# microzed_breakout_v0_7_b6e30659.net
KiCad netlist of a schematic drawn in EAGLE
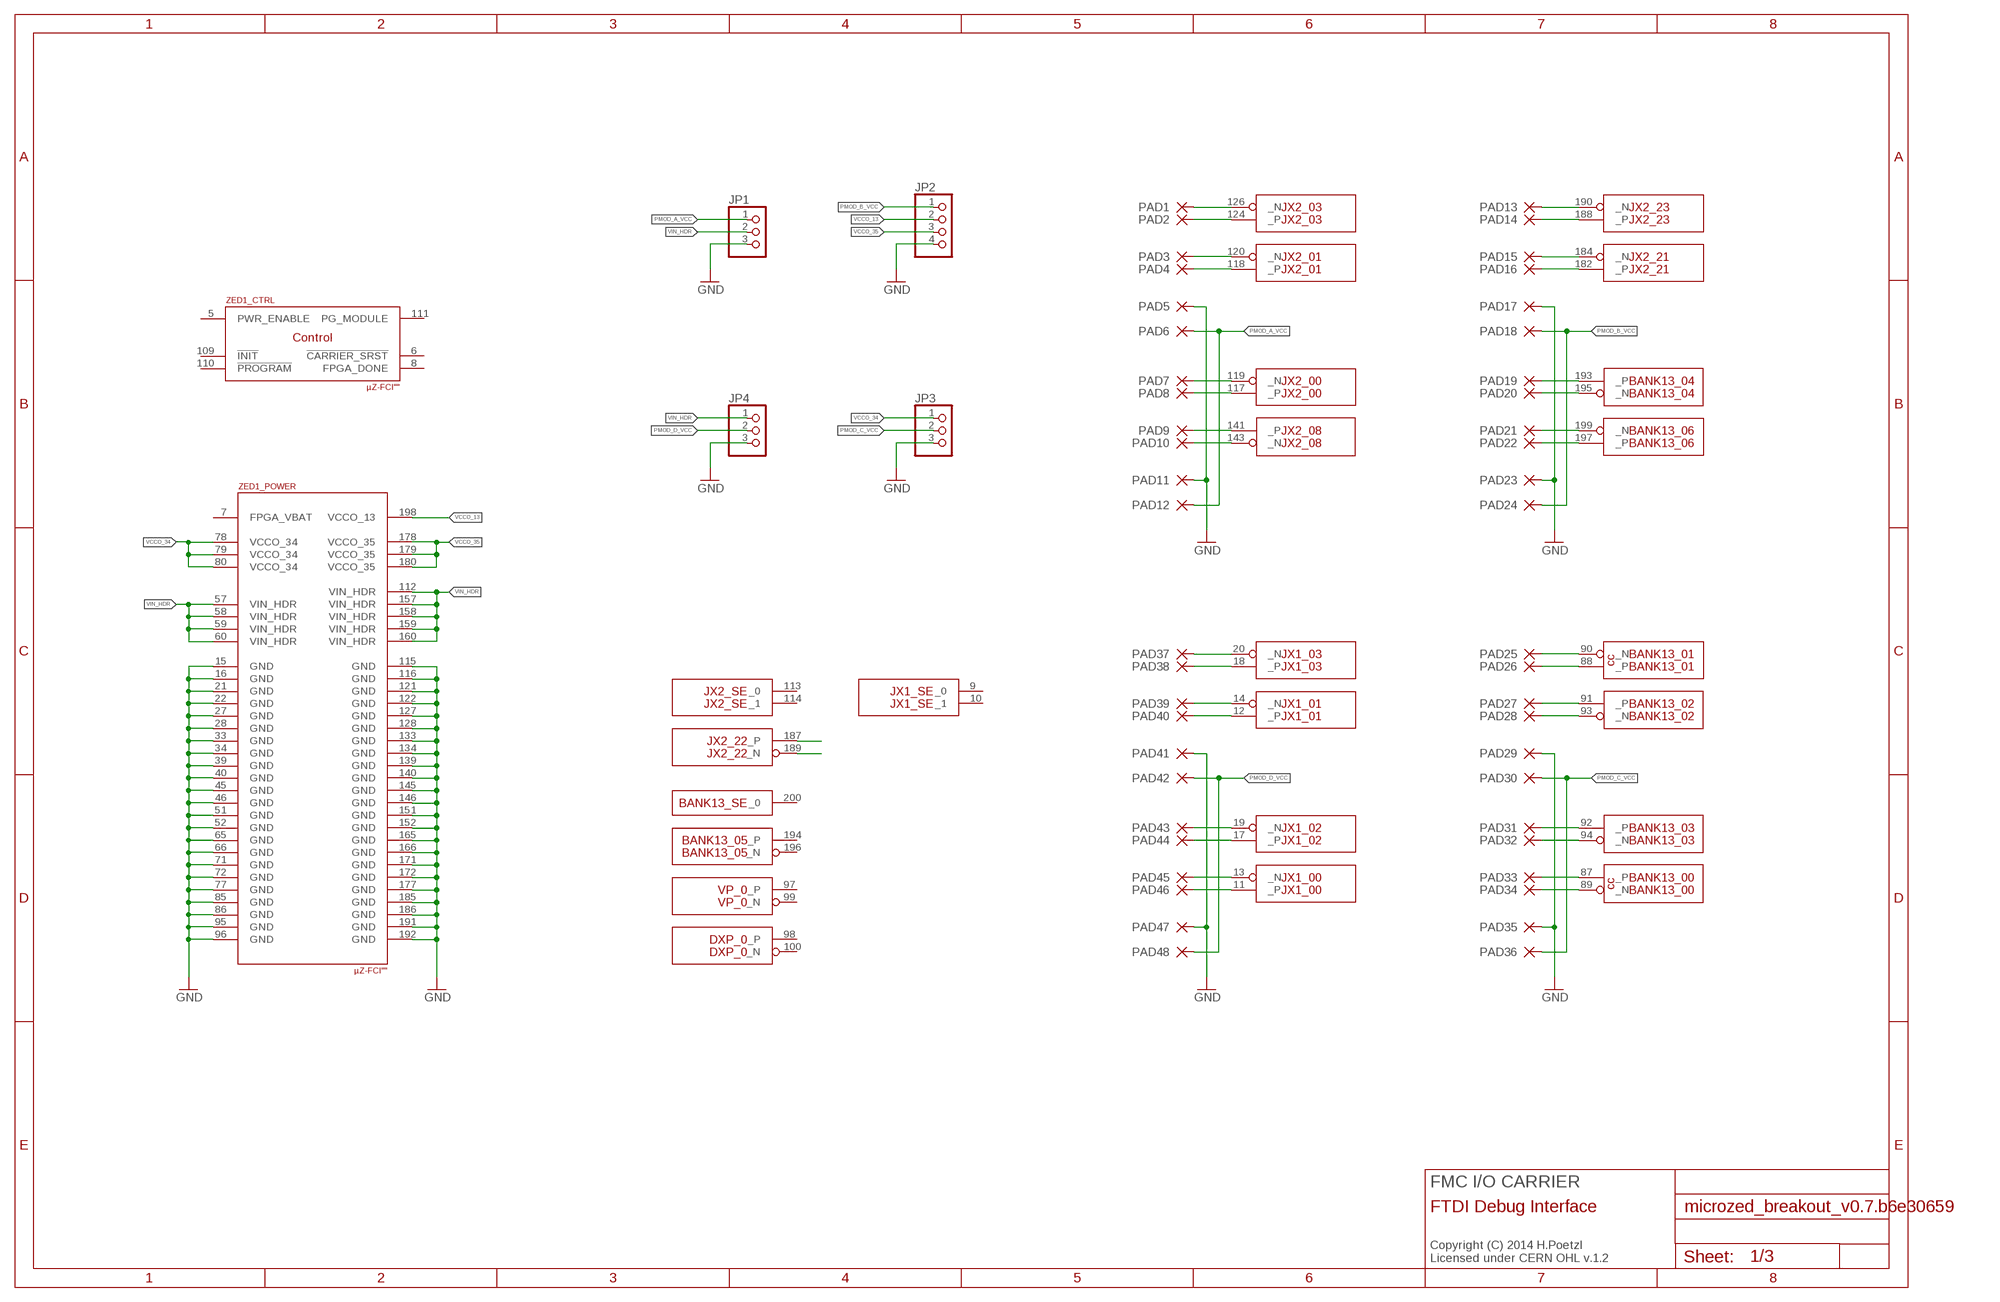
[diagram p0: schematic, sheet 1]
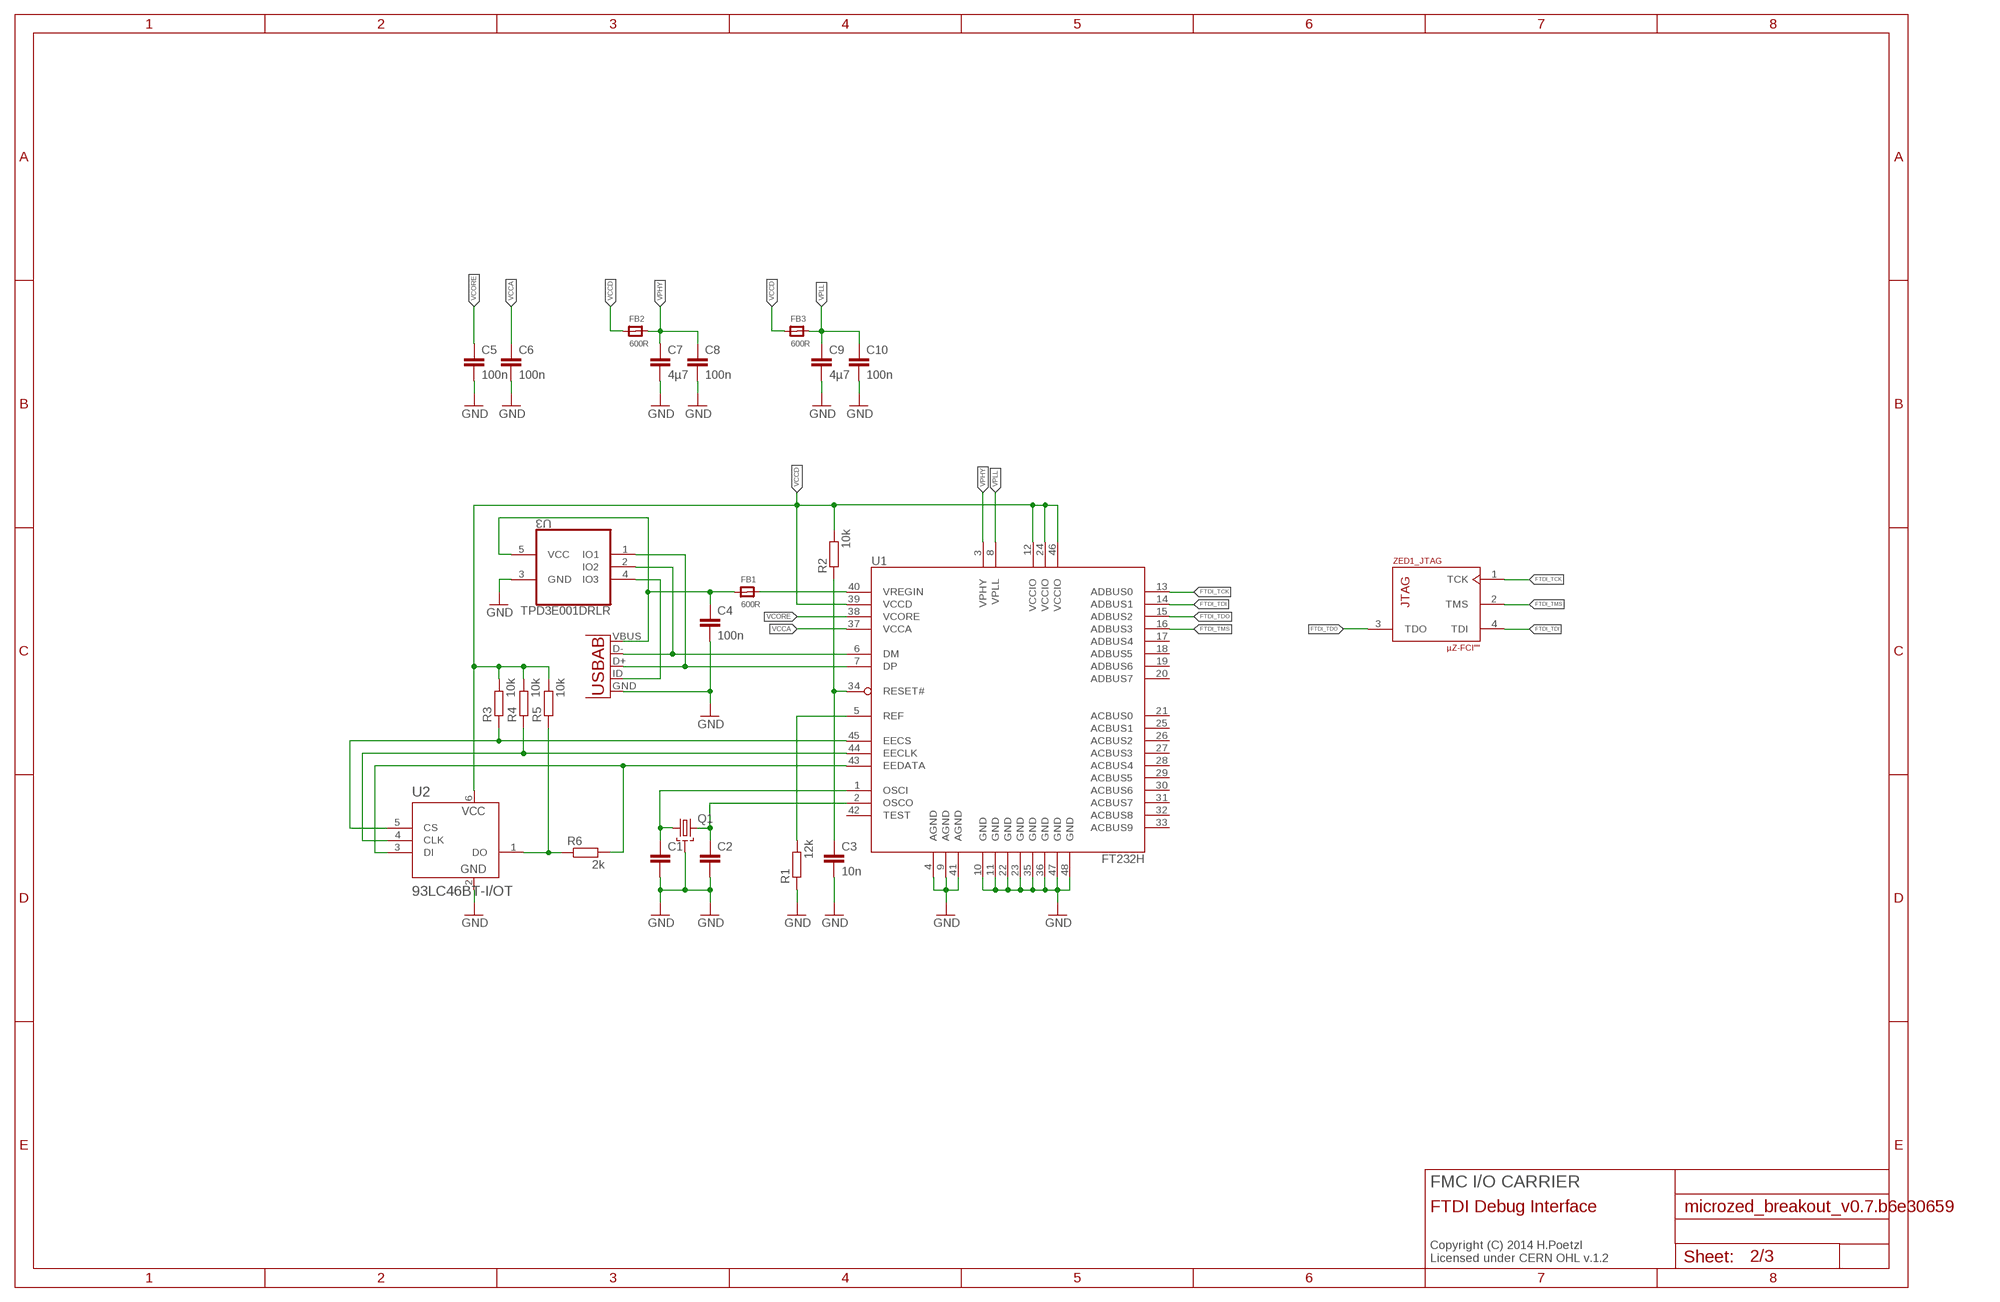
[diagram p1: schematic, sheet 2]
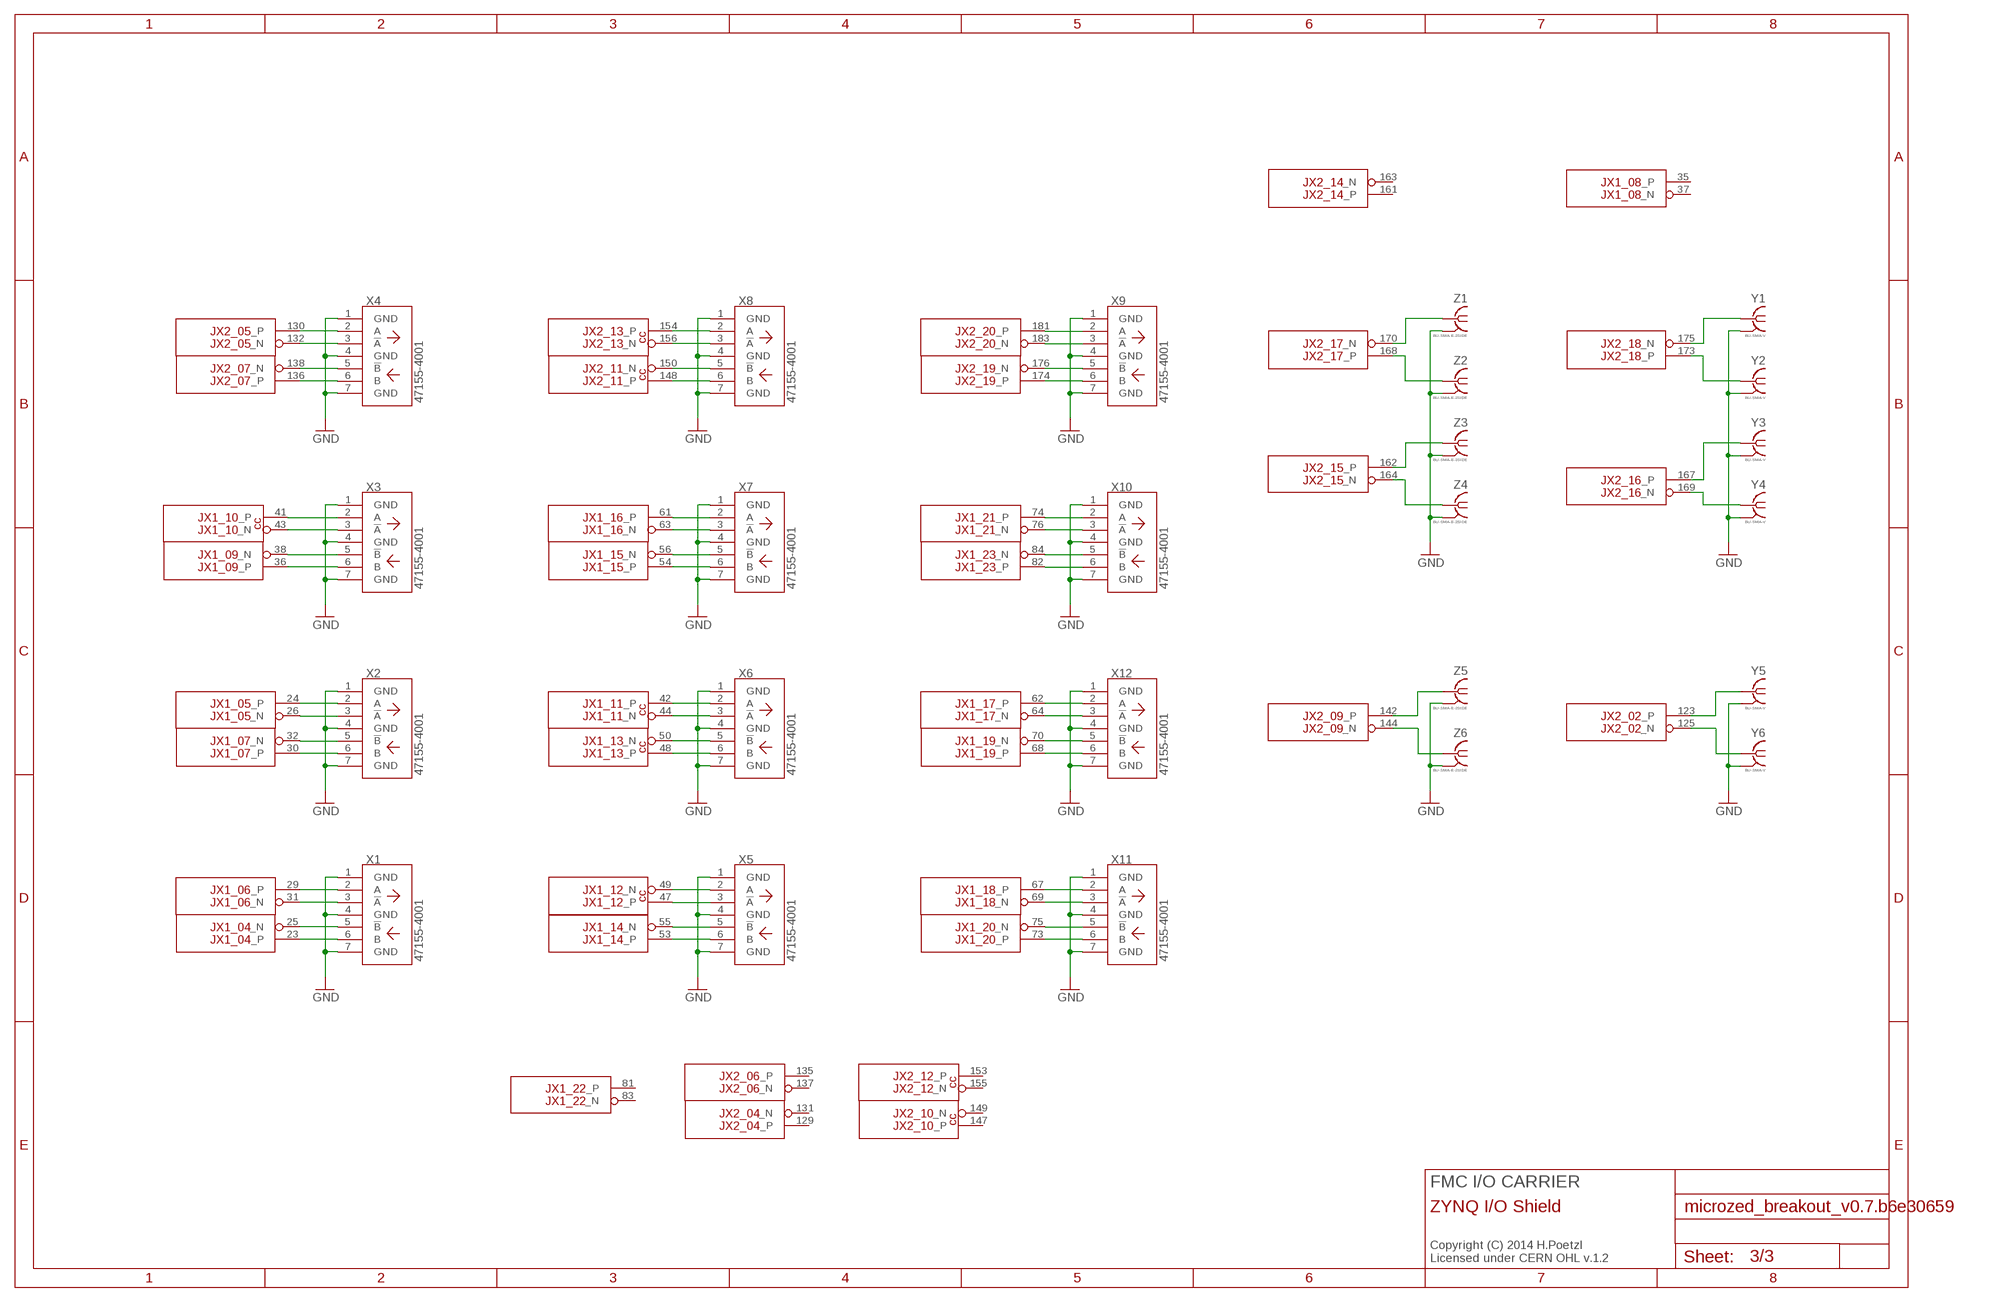
[diagram p2: schematic, sheet 3]

(export (version "E")
  (design (tool "Eeschema 10.0.6"))
  (components
    (comp (ref "C1")
      (value "C-EUC0402K")
      (footprint "eagle-import:C0402K")
      (libsource (lib "eagle-import") (part "C-EUC0402K"))
    )
    (comp (ref "C2")
      (value "C-EUC0402K")
      (footprint "eagle-import:C0402K")
      (libsource (lib "eagle-import") (part "C-EUC0402K"))
    )
    (comp (ref "C3")
      (value "10n")
      (footprint "eagle-import:C0402K")
      (libsource (lib "eagle-import") (part "C-EUC0402K"))
    )
    (comp (ref "C4")
      (value "100n")
      (footprint "eagle-import:C0402K")
      (libsource (lib "eagle-import") (part "C-EUC0402K"))
    )
    (comp (ref "C5")
      (value "100n")
      (footprint "eagle-import:C0402K")
      (libsource (lib "eagle-import") (part "C-EUC0402K"))
    )
    (comp (ref "C6")
      (value "100n")
      (footprint "eagle-import:C0402K")
      (libsource (lib "eagle-import") (part "C-EUC0402K"))
    )
    (comp (ref "C7")
      (value "4µ7")
      (footprint "eagle-import:C0402K")
      (libsource (lib "eagle-import") (part "C-EUC0402K"))
    )
    (comp (ref "C8")
      (value "100n")
      (footprint "eagle-import:C0402K")
      (libsource (lib "eagle-import") (part "C-EUC0402K"))
    )
    (comp (ref "C9")
      (value "4µ7")
      (footprint "eagle-import:C0402K")
      (libsource (lib "eagle-import") (part "C-EUC0402K"))
    )
    (comp (ref "C10")
      (value "100n")
      (footprint "eagle-import:C0402K")
      (libsource (lib "eagle-import") (part "C-EUC0402K"))
    )
    (comp (ref "FB1")
      (value "600R")
      (footprint "eagle-import:_0603MP")
      (libsource (lib "eagle-import") (part "FERRITE_0603MP"))
    )
    (comp (ref "FB2")
      (value "600R")
      (footprint "eagle-import:_0603MP")
      (libsource (lib "eagle-import") (part "FERRITE_0603MP"))
    )
    (comp (ref "FB3")
      (value "600R")
      (footprint "eagle-import:_0603MP")
      (libsource (lib "eagle-import") (part "FERRITE_0603MP"))
    )
    (comp (ref "Q1")
      (value "SMD-4P-2G-3.2X2.5")
      (footprint "eagle-import:ABM8G")
      (libsource (lib "eagle-import") (part "SMD-4P-2G-3.2X2.5"))
    )
    (comp (ref "R1")
      (value "12k")
      (footprint "eagle-import:R0402")
      (libsource (lib "eagle-import") (part "R-EU_R0402"))
    )
    (comp (ref "R2")
      (value "10k")
      (footprint "eagle-import:R0402")
      (libsource (lib "eagle-import") (part "R-EU_R0402"))
    )
    (comp (ref "R3")
      (value "10k")
      (footprint "eagle-import:R0402")
      (libsource (lib "eagle-import") (part "R-EU_R0402"))
    )
    (comp (ref "R4")
      (value "10k")
      (footprint "eagle-import:R0402")
      (libsource (lib "eagle-import") (part "R-EU_R0402"))
    )
    (comp (ref "R5")
      (value "10k")
      (footprint "eagle-import:R0402")
      (libsource (lib "eagle-import") (part "R-EU_R0402"))
    )
    (comp (ref "R6")
      (value "2k")
      (footprint "eagle-import:R0402")
      (libsource (lib "eagle-import") (part "R-EU_R0402"))
    )
    (comp (ref "U1")
      (value "FT232H")
      (footprint "eagle-import:LQFP48")
      (libsource (lib "eagle-import") (part "FT232H"))
    )
    (comp (ref "U2")
      (value "93LC46BT-I/OT")
      (footprint "eagle-import:SOT95P280X145-6N")
      (libsource (lib "eagle-import") (part "93LC46BT-I/OT"))
    )
    (comp (ref "U3")
      (value "TPD3E001DRLR")
      (footprint "eagle-import:SOT50P160X60-5N")
      (libsource (lib "eagle-import") (part "TPD3E001DRLR"))
    )
    (comp (ref "USB")
      (value "USB-AB")
      (footprint "eagle-import:USB-AB-MICRO-SMD")
      (libsource (lib "eagle-import") (part "USB-AB"))
    )
    (comp (ref "ZED1")
      (value "µZ-FCI\"\"")
      (footprint "eagle-import:µZ")
      (libsource (lib "eagle-import") (part "µZ-FCI{dblquote}{dblquote}"))
    )
    (comp (ref "X1")
      (value "47155-4001")
      (footprint "eagle-import:SATA7-VERT")
      (libsource (lib "eagle-import") (part "SATA7-VERT"))
    )
    (comp (ref "X2")
      (value "47155-4001")
      (footprint "eagle-import:SATA7-VERT")
      (libsource (lib "eagle-import") (part "SATA7-VERT"))
    )
    (comp (ref "X3")
      (value "47155-4001")
      (footprint "eagle-import:SATA7-VERT")
      (libsource (lib "eagle-import") (part "SATA7-VERT"))
    )
    (comp (ref "X4")
      (value "47155-4001")
      (footprint "eagle-import:SATA7-VERT")
      (libsource (lib "eagle-import") (part "SATA7-VERT"))
    )
    (comp (ref "X5")
      (value "47155-4001")
      (footprint "eagle-import:SATA7-VERT")
      (libsource (lib "eagle-import") (part "SATA7-VERT"))
    )
    (comp (ref "X6")
      (value "47155-4001")
      (footprint "eagle-import:SATA7-VERT")
      (libsource (lib "eagle-import") (part "SATA7-VERT"))
    )
    (comp (ref "X7")
      (value "47155-4001")
      (footprint "eagle-import:SATA7-VERT")
      (libsource (lib "eagle-import") (part "SATA7-VERT"))
    )
    (comp (ref "X8")
      (value "47155-4001")
      (footprint "eagle-import:SATA7-VERT")
      (libsource (lib "eagle-import") (part "SATA7-VERT"))
    )
    (comp (ref "X9")
      (value "47155-4001")
      (footprint "eagle-import:SATA7-VERT")
      (libsource (lib "eagle-import") (part "SATA7-VERT"))
    )
    (comp (ref "X10")
      (value "47155-4001")
      (footprint "eagle-import:SATA7-VERT")
      (libsource (lib "eagle-import") (part "SATA7-VERT"))
    )
    (comp (ref "X11")
      (value "47155-4001")
      (footprint "eagle-import:SATA7-VERT")
      (libsource (lib "eagle-import") (part "SATA7-VERT"))
    )
    (comp (ref "X12")
      (value "47155-4001")
      (footprint "eagle-import:SATA7-VERT")
      (libsource (lib "eagle-import") (part "SATA7-VERT"))
    )
    (comp (ref "Y1")
      (value "BU-SMA-V")
      (footprint "eagle-import:BU-SMA-V")
      (libsource (lib "eagle-import") (part "BU-SMA-V"))
    )
    (comp (ref "Y2")
      (value "BU-SMA-V")
      (footprint "eagle-import:BU-SMA-V")
      (libsource (lib "eagle-import") (part "BU-SMA-V"))
    )
    (comp (ref "Y3")
      (value "BU-SMA-V")
      (footprint "eagle-import:BU-SMA-V")
      (libsource (lib "eagle-import") (part "BU-SMA-V"))
    )
    (comp (ref "Y4")
      (value "BU-SMA-V")
      (footprint "eagle-import:BU-SMA-V")
      (libsource (lib "eagle-import") (part "BU-SMA-V"))
    )
    (comp (ref "Y5")
      (value "BU-SMA-V")
      (footprint "eagle-import:BU-SMA-V")
      (libsource (lib "eagle-import") (part "BU-SMA-V"))
    )
    (comp (ref "Y6")
      (value "BU-SMA-V")
      (footprint "eagle-import:BU-SMA-V")
      (libsource (lib "eagle-import") (part "BU-SMA-V"))
    )
    (comp (ref "Z1")
      (value "BU-SMA-E-2SIDE")
      (footprint "eagle-import:SMA_EDGE_2SIDE")
      (libsource (lib "eagle-import") (part "BU-SMA-E-2SIDE"))
    )
    (comp (ref "Z2")
      (value "BU-SMA-E-2SIDE")
      (footprint "eagle-import:SMA_EDGE_2SIDE")
      (libsource (lib "eagle-import") (part "BU-SMA-E-2SIDE"))
    )
    (comp (ref "Z3")
      (value "BU-SMA-E-2SIDE")
      (footprint "eagle-import:SMA_EDGE_2SIDE")
      (libsource (lib "eagle-import") (part "BU-SMA-E-2SIDE"))
    )
    (comp (ref "Z4")
      (value "BU-SMA-E-2SIDE")
      (footprint "eagle-import:SMA_EDGE_2SIDE")
      (libsource (lib "eagle-import") (part "BU-SMA-E-2SIDE"))
    )
    (comp (ref "Z5")
      (value "BU-SMA-E-2SIDE")
      (footprint "eagle-import:SMA_EDGE_2SIDE")
      (libsource (lib "eagle-import") (part "BU-SMA-E-2SIDE"))
    )
    (comp (ref "Z6")
      (value "BU-SMA-E-2SIDE")
      (footprint "eagle-import:SMA_EDGE_2SIDE")
      (libsource (lib "eagle-import") (part "BU-SMA-E-2SIDE"))
    )
    (comp (ref "JP1")
      (value "PINHD-1X03_2.54")
      (footprint "eagle-import:1X03")
      (libsource (lib "eagle-import") (part "PINHD-1X03_2.54"))
    )
    (comp (ref "JP2")
      (value "PINHD-1X04_2.54")
      (footprint "eagle-import:1X04")
      (libsource (lib "eagle-import") (part "PINHD-1X04_2.54"))
    )
    (comp (ref "JP3")
      (value "PINHD-1X03_2.54")
      (footprint "eagle-import:1X03")
      (libsource (lib "eagle-import") (part "PINHD-1X03_2.54"))
    )
    (comp (ref "JP4")
      (value "PINHD-1X03_2.54")
      (footprint "eagle-import:1X03")
      (libsource (lib "eagle-import") (part "PINHD-1X03_2.54"))
    )
    (comp (ref "PAD1")
      (value "SMD-PAD1.6X3.8MM-U")
      (footprint "eagle-import:1.6X3.8U-MM")
      (libsource (lib "eagle-import") (part "SMD-PAD1.6X3.8MM-U"))
    )
    (comp (ref "PAD2")
      (value "SMD-PAD1.6X3.8MM-U")
      (footprint "eagle-import:1.6X3.8U-MM")
      (libsource (lib "eagle-import") (part "SMD-PAD1.6X3.8MM-U"))
    )
    (comp (ref "PAD3")
      (value "SMD-PAD1.6X3.8MM-U")
      (footprint "eagle-import:1.6X3.8U-MM")
      (libsource (lib "eagle-import") (part "SMD-PAD1.6X3.8MM-U"))
    )
    (comp (ref "PAD4")
      (value "SMD-PAD1.6X3.8MM-U")
      (footprint "eagle-import:1.6X3.8U-MM")
      (libsource (lib "eagle-import") (part "SMD-PAD1.6X3.8MM-U"))
    )
    (comp (ref "PAD5")
      (value "SMD-PAD1.6X3.8MM-U")
      (footprint "eagle-import:1.6X3.8U-MM")
      (libsource (lib "eagle-import") (part "SMD-PAD1.6X3.8MM-U"))
    )
    (comp (ref "PAD6")
      (value "SMD-PAD1.6X3.8MM-U")
      (footprint "eagle-import:1.6X3.8U-MM")
      (libsource (lib "eagle-import") (part "SMD-PAD1.6X3.8MM-U"))
    )
    (comp (ref "PAD7")
      (value "SMD-PAD1.6X3.8MM-U")
      (footprint "eagle-import:1.6X3.8U-MM")
      (libsource (lib "eagle-import") (part "SMD-PAD1.6X3.8MM-U"))
    )
    (comp (ref "PAD8")
      (value "SMD-PAD1.6X3.8MM-U")
      (footprint "eagle-import:1.6X3.8U-MM")
      (libsource (lib "eagle-import") (part "SMD-PAD1.6X3.8MM-U"))
    )
    (comp (ref "PAD9")
      (value "SMD-PAD1.6X3.8MM-U")
      (footprint "eagle-import:1.6X3.8U-MM")
      (libsource (lib "eagle-import") (part "SMD-PAD1.6X3.8MM-U"))
    )
    (comp (ref "PAD10")
      (value "SMD-PAD1.6X3.8MM-U")
      (footprint "eagle-import:1.6X3.8U-MM")
      (libsource (lib "eagle-import") (part "SMD-PAD1.6X3.8MM-U"))
    )
    (comp (ref "PAD11")
      (value "SMD-PAD1.6X3.8MM-U")
      (footprint "eagle-import:1.6X3.8U-MM")
      (libsource (lib "eagle-import") (part "SMD-PAD1.6X3.8MM-U"))
    )
    (comp (ref "PAD12")
      (value "SMD-PAD1.6X3.8MM-U")
      (footprint "eagle-import:1.6X3.8U-MM")
      (libsource (lib "eagle-import") (part "SMD-PAD1.6X3.8MM-U"))
    )
    (comp (ref "PAD13")
      (value "SMD-PAD1.6X3.8MM-U")
      (footprint "eagle-import:1.6X3.8U-MM")
      (libsource (lib "eagle-import") (part "SMD-PAD1.6X3.8MM-U"))
    )
    (comp (ref "PAD14")
      (value "SMD-PAD1.6X3.8MM-U")
      (footprint "eagle-import:1.6X3.8U-MM")
      (libsource (lib "eagle-import") (part "SMD-PAD1.6X3.8MM-U"))
    )
    (comp (ref "PAD15")
      (value "SMD-PAD1.6X3.8MM-U")
      (footprint "eagle-import:1.6X3.8U-MM")
      (libsource (lib "eagle-import") (part "SMD-PAD1.6X3.8MM-U"))
    )
    (comp (ref "PAD16")
      (value "SMD-PAD1.6X3.8MM-U")
      (footprint "eagle-import:1.6X3.8U-MM")
      (libsource (lib "eagle-import") (part "SMD-PAD1.6X3.8MM-U"))
    )
    (comp (ref "PAD17")
      (value "SMD-PAD1.6X3.8MM-U")
      (footprint "eagle-import:1.6X3.8U-MM")
      (libsource (lib "eagle-import") (part "SMD-PAD1.6X3.8MM-U"))
    )
    (comp (ref "PAD18")
      (value "SMD-PAD1.6X3.8MM-U")
      (footprint "eagle-import:1.6X3.8U-MM")
      (libsource (lib "eagle-import") (part "SMD-PAD1.6X3.8MM-U"))
    )
    (comp (ref "PAD19")
      (value "SMD-PAD1.6X3.8MM-U")
      (footprint "eagle-import:1.6X3.8U-MM")
      (libsource (lib "eagle-import") (part "SMD-PAD1.6X3.8MM-U"))
    )
    (comp (ref "PAD20")
      (value "SMD-PAD1.6X3.8MM-U")
      (footprint "eagle-import:1.6X3.8U-MM")
      (libsource (lib "eagle-import") (part "SMD-PAD1.6X3.8MM-U"))
    )
    (comp (ref "PAD21")
      (value "SMD-PAD1.6X3.8MM-U")
      (footprint "eagle-import:1.6X3.8U-MM")
      (libsource (lib "eagle-import") (part "SMD-PAD1.6X3.8MM-U"))
    )
    (comp (ref "PAD22")
      (value "SMD-PAD1.6X3.8MM-U")
      (footprint "eagle-import:1.6X3.8U-MM")
      (libsource (lib "eagle-import") (part "SMD-PAD1.6X3.8MM-U"))
    )
    (comp (ref "PAD23")
      (value "SMD-PAD1.6X3.8MM-U")
      (footprint "eagle-import:1.6X3.8U-MM")
      (libsource (lib "eagle-import") (part "SMD-PAD1.6X3.8MM-U"))
    )
    (comp (ref "PAD24")
      (value "SMD-PAD1.6X3.8MM-U")
      (footprint "eagle-import:1.6X3.8U-MM")
      (libsource (lib "eagle-import") (part "SMD-PAD1.6X3.8MM-U"))
    )
    (comp (ref "PAD25")
      (value "SMD-PAD1.6X3.8MM-U")
      (footprint "eagle-import:1.6X3.8U-MM")
      (libsource (lib "eagle-import") (part "SMD-PAD1.6X3.8MM-U"))
    )
    (comp (ref "PAD26")
      (value "SMD-PAD1.6X3.8MM-U")
      (footprint "eagle-import:1.6X3.8U-MM")
      (libsource (lib "eagle-import") (part "SMD-PAD1.6X3.8MM-U"))
    )
    (comp (ref "PAD27")
      (value "SMD-PAD1.6X3.8MM-U")
      (footprint "eagle-import:1.6X3.8U-MM")
      (libsource (lib "eagle-import") (part "SMD-PAD1.6X3.8MM-U"))
    )
    (comp (ref "PAD28")
      (value "SMD-PAD1.6X3.8MM-U")
      (footprint "eagle-import:1.6X3.8U-MM")
      (libsource (lib "eagle-import") (part "SMD-PAD1.6X3.8MM-U"))
    )
    (comp (ref "PAD29")
      (value "SMD-PAD1.6X3.8MM-U")
      (footprint "eagle-import:1.6X3.8U-MM")
      (libsource (lib "eagle-import") (part "SMD-PAD1.6X3.8MM-U"))
    )
    (comp (ref "PAD30")
      (value "SMD-PAD1.6X3.8MM-U")
      (footprint "eagle-import:1.6X3.8U-MM")
      (libsource (lib "eagle-import") (part "SMD-PAD1.6X3.8MM-U"))
    )
    (comp (ref "PAD31")
      (value "SMD-PAD1.6X3.8MM-U")
      (footprint "eagle-import:1.6X3.8U-MM")
      (libsource (lib "eagle-import") (part "SMD-PAD1.6X3.8MM-U"))
    )
    (comp (ref "PAD32")
      (value "SMD-PAD1.6X3.8MM-U")
      (footprint "eagle-import:1.6X3.8U-MM")
      (libsource (lib "eagle-import") (part "SMD-PAD1.6X3.8MM-U"))
    )
    (comp (ref "PAD33")
      (value "SMD-PAD1.6X3.8MM-U")
      (footprint "eagle-import:1.6X3.8U-MM")
      (libsource (lib "eagle-import") (part "SMD-PAD1.6X3.8MM-U"))
    )
    (comp (ref "PAD34")
      (value "SMD-PAD1.6X3.8MM-U")
      (footprint "eagle-import:1.6X3.8U-MM")
      (libsource (lib "eagle-import") (part "SMD-PAD1.6X3.8MM-U"))
    )
    (comp (ref "PAD35")
      (value "SMD-PAD1.6X3.8MM-U")
      (footprint "eagle-import:1.6X3.8U-MM")
      (libsource (lib "eagle-import") (part "SMD-PAD1.6X3.8MM-U"))
    )
    (comp (ref "PAD36")
      (value "SMD-PAD1.6X3.8MM-U")
      (footprint "eagle-import:1.6X3.8U-MM")
      (libsource (lib "eagle-import") (part "SMD-PAD1.6X3.8MM-U"))
    )
    (comp (ref "PAD37")
      (value "SMD-PAD1.6X3.8MM-U")
      (footprint "eagle-import:1.6X3.8U-MM")
      (libsource (lib "eagle-import") (part "SMD-PAD1.6X3.8MM-U"))
    )
    (comp (ref "PAD38")
      (value "SMD-PAD1.6X3.8MM-U")
      (footprint "eagle-import:1.6X3.8U-MM")
      (libsource (lib "eagle-import") (part "SMD-PAD1.6X3.8MM-U"))
    )
    (comp (ref "PAD39")
      (value "SMD-PAD1.6X3.8MM-U")
      (footprint "eagle-import:1.6X3.8U-MM")
      (libsource (lib "eagle-import") (part "SMD-PAD1.6X3.8MM-U"))
    )
    (comp (ref "PAD40")
      (value "SMD-PAD1.6X3.8MM-U")
      (footprint "eagle-import:1.6X3.8U-MM")
      (libsource (lib "eagle-import") (part "SMD-PAD1.6X3.8MM-U"))
    )
    (comp (ref "PAD41")
      (value "SMD-PAD1.6X3.8MM-U")
      (footprint "eagle-import:1.6X3.8U-MM")
      (libsource (lib "eagle-import") (part "SMD-PAD1.6X3.8MM-U"))
    )
    (comp (ref "PAD42")
      (value "SMD-PAD1.6X3.8MM-U")
      (footprint "eagle-import:1.6X3.8U-MM")
      (libsource (lib "eagle-import") (part "SMD-PAD1.6X3.8MM-U"))
    )
    (comp (ref "PAD43")
      (value "SMD-PAD1.6X3.8MM-U")
      (footprint "eagle-import:1.6X3.8U-MM")
      (libsource (lib "eagle-import") (part "SMD-PAD1.6X3.8MM-U"))
    )
    (comp (ref "PAD44")
      (value "SMD-PAD1.6X3.8MM-U")
      (footprint "eagle-import:1.6X3.8U-MM")
      (libsource (lib "eagle-import") (part "SMD-PAD1.6X3.8MM-U"))
    )
    (comp (ref "PAD45")
      (value "SMD-PAD1.6X3.8MM-U")
      (footprint "eagle-import:1.6X3.8U-MM")
      (libsource (lib "eagle-import") (part "SMD-PAD1.6X3.8MM-U"))
    )
    (comp (ref "PAD46")
      (value "SMD-PAD1.6X3.8MM-U")
      (footprint "eagle-import:1.6X3.8U-MM")
      (libsource (lib "eagle-import") (part "SMD-PAD1.6X3.8MM-U"))
    )
    (comp (ref "PAD47")
      (value "SMD-PAD1.6X3.8MM-U")
      (footprint "eagle-import:1.6X3.8U-MM")
      (libsource (lib "eagle-import") (part "SMD-PAD1.6X3.8MM-U"))
    )
    (comp (ref "PAD48")
      (value "SMD-PAD1.6X3.8MM-U")
      (footprint "eagle-import:1.6X3.8U-MM")
      (libsource (lib "eagle-import") (part "SMD-PAD1.6X3.8MM-U"))
    )
  )
  (nets
    (net (code "1") (name "FPGA_VBAT") (class "Default")
      (node (ref "ZED1") (pin "7") (pinfunction "FPGA_VBAT_7") (pintype "power_in"))
    )
    (net (code "2") (name "FTDI_TCK") (class "Default")
      (node (ref "U1") (pin "13") (pinfunction "ADBUS0_13") (pintype "output"))
      (node (ref "ZED1") (pin "1") (pinfunction "TCK_1") (pintype "output"))
    )
    (net (code "3") (name "FTDI_TDI") (class "Default")
      (node (ref "U1") (pin "14") (pinfunction "ADBUS1_14") (pintype "input"))
      (node (ref "ZED1") (pin "4") (pinfunction "TDI_4") (pintype "output"))
    )
    (net (code "4") (name "FTDI_TDO") (class "Default")
      (node (ref "U1") (pin "15") (pinfunction "ADBUS2_15") (pintype "output"))
      (node (ref "ZED1") (pin "3") (pinfunction "TDO_3") (pintype "input"))
    )
    (net (code "5") (name "FTDI_TMS") (class "Default")
      (node (ref "U1") (pin "16") (pinfunction "ADBUS3_16") (pintype "input"))
      (node (ref "ZED1") (pin "2") (pinfunction "TMS_2") (pintype "output"))
    )
    (net (code "6") (name "GND") (class "Default")
      (node (ref "C1") (pin "2") (pinfunction "2_2") (pintype "passive"))
      (node (ref "C10") (pin "2") (pinfunction "2_2") (pintype "passive"))
      (node (ref "C2") (pin "2") (pinfunction "2_2") (pintype "passive"))
      (node (ref "C3") (pin "2") (pinfunction "2_2") (pintype "passive"))
      (node (ref "C4") (pin "2") (pinfunction "2_2") (pintype "passive"))
      (node (ref "C5") (pin "2") (pinfunction "2_2") (pintype "passive"))
      (node (ref "C6") (pin "2") (pinfunction "2_2") (pintype "passive"))
      (node (ref "C7") (pin "2") (pinfunction "2_2") (pintype "passive"))
      (node (ref "C8") (pin "2") (pinfunction "2_2") (pintype "passive"))
      (node (ref "C9") (pin "2") (pinfunction "2_2") (pintype "passive"))
      (node (ref "JP1") (pin "3") (pinfunction "3_3") (pintype "passive"))
      (node (ref "JP2") (pin "4") (pinfunction "4_4") (pintype "passive"))
      (node (ref "JP3") (pin "3") (pinfunction "3_3") (pintype "passive"))
      (node (ref "JP4") (pin "3") (pinfunction "3_3") (pintype "passive"))
      (node (ref "PAD11") (pin "1") (pinfunction "P_1") (pintype "passive"))
      (node (ref "PAD17") (pin "1") (pinfunction "P_1") (pintype "passive"))
      (node (ref "PAD23") (pin "1") (pinfunction "P_1") (pintype "passive"))
      (node (ref "PAD29") (pin "1") (pinfunction "P_1") (pintype "passive"))
      (node (ref "PAD35") (pin "1") (pinfunction "P_1") (pintype "passive"))
      (node (ref "PAD41") (pin "1") (pinfunction "P_1") (pintype "passive"))
      (node (ref "PAD47") (pin "1") (pinfunction "P_1") (pintype "passive"))
      (node (ref "PAD5") (pin "1") (pinfunction "P_1") (pintype "passive"))
      (node (ref "Q1") (pin "2") (pinfunction "GND_2") (pintype "power_in"))
      (node (ref "Q1") (pin "4") (pinfunction "GND_4") (pintype "power_in"))
      (node (ref "R1") (pin "1") (pinfunction "1_1") (pintype "passive"))
      (node (ref "U1") (pin "10") (pinfunction "GND_10") (pintype "power_in"))
      (node (ref "U1") (pin "11") (pinfunction "GND_11") (pintype "power_in"))
      (node (ref "U1") (pin "22") (pinfunction "GND_22") (pintype "power_in"))
      (node (ref "U1") (pin "23") (pinfunction "GND_23") (pintype "power_in"))
      (node (ref "U1") (pin "35") (pinfunction "GND_35") (pintype "power_in"))
      (node (ref "U1") (pin "36") (pinfunction "GND_36") (pintype "power_in"))
      (node (ref "U1") (pin "4") (pinfunction "AGND_4") (pintype "power_in"))
      (node (ref "U1") (pin "41") (pinfunction "AGND_41") (pintype "power_in"))
      (node (ref "U1") (pin "47") (pinfunction "GND_47") (pintype "power_in"))
      (node (ref "U1") (pin "48") (pinfunction "GND_48") (pintype "power_in"))
      (node (ref "U1") (pin "9") (pinfunction "AGND_9") (pintype "power_in"))
      (node (ref "U2") (pin "2") (pinfunction "VSS_2") (pintype "power_in"))
      (node (ref "U3") (pin "3") (pinfunction "GND_3") (pintype "passive"))
      (node (ref "USB") (pin "GND") (pinfunction "GND_GND") (pintype "bidirectional"))
      (node (ref "X1") (pin "1") (pinfunction "GND_1") (pintype "passive"))
      (node (ref "X1") (pin "4") (pinfunction "GND_4") (pintype "passive"))
      (node (ref "X1") (pin "7") (pinfunction "GND_7") (pintype "passive"))
      (node (ref "X10") (pin "1") (pinfunction "GND_1") (pintype "passive"))
      (node (ref "X10") (pin "4") (pinfunction "GND_4") (pintype "passive"))
      (node (ref "X10") (pin "7") (pinfunction "GND_7") (pintype "passive"))
      (node (ref "X11") (pin "1") (pinfunction "GND_1") (pintype "passive"))
      (node (ref "X11") (pin "4") (pinfunction "GND_4") (pintype "passive"))
      (node (ref "X11") (pin "7") (pinfunction "GND_7") (pintype "passive"))
      (node (ref "X12") (pin "1") (pinfunction "GND_1") (pintype "passive"))
      (node (ref "X12") (pin "4") (pinfunction "GND_4") (pintype "passive"))
      (node (ref "X12") (pin "7") (pinfunction "GND_7") (pintype "passive"))
      (node (ref "X2") (pin "1") (pinfunction "GND_1") (pintype "passive"))
      (node (ref "X2") (pin "4") (pinfunction "GND_4") (pintype "passive"))
      (node (ref "X2") (pin "7") (pinfunction "GND_7") (pintype "passive"))
      (node (ref "X3") (pin "1") (pinfunction "GND_1") (pintype "passive"))
      (node (ref "X3") (pin "4") (pinfunction "GND_4") (pintype "passive"))
      (node (ref "X3") (pin "7") (pinfunction "GND_7") (pintype "passive"))
      (node (ref "X4") (pin "1") (pinfunction "GND_1") (pintype "passive"))
      (node (ref "X4") (pin "4") (pinfunction "GND_4") (pintype "passive"))
      (node (ref "X4") (pin "7") (pinfunction "GND_7") (pintype "passive"))
      (node (ref "X5") (pin "1") (pinfunction "GND_1") (pintype "passive"))
      (node (ref "X5") (pin "4") (pinfunction "GND_4") (pintype "passive"))
      (node (ref "X5") (pin "7") (pinfunction "GND_7") (pintype "passive"))
      (node (ref "X6") (pin "1") (pinfunction "GND_1") (pintype "passive"))
      (node (ref "X6") (pin "4") (pinfunction "GND_4") (pintype "passive"))
      (node (ref "X6") (pin "7") (pinfunction "GND_7") (pintype "passive"))
      (node (ref "X7") (pin "1") (pinfunction "GND_1") (pintype "passive"))
      (node (ref "X7") (pin "4") (pinfunction "GND_4") (pintype "passive"))
      (node (ref "X7") (pin "7") (pinfunction "GND_7") (pintype "passive"))
      (node (ref "X8") (pin "1") (pinfunction "GND_1") (pintype "passive"))
      (node (ref "X8") (pin "4") (pinfunction "GND_4") (pintype "passive"))
      (node (ref "X8") (pin "7") (pinfunction "GND_7") (pintype "passive"))
      (node (ref "X9") (pin "1") (pinfunction "GND_1") (pintype "passive"))
      (node (ref "X9") (pin "4") (pinfunction "GND_4") (pintype "passive"))
      (node (ref "X9") (pin "7") (pinfunction "GND_7") (pintype "passive"))
      (node (ref "Y1") (pin "2") (pinfunction "2_2") (pintype "passive"))
      (node (ref "Y1") (pin "3") (pinfunction "2_3") (pintype "passive"))
      (node (ref "Y1") (pin "4") (pinfunction "2_4") (pintype "passive"))
      (node (ref "Y1") (pin "5") (pinfunction "2_5") (pintype "passive"))
      (node (ref "Y2") (pin "2") (pinfunction "2_2") (pintype "passive"))
      (node (ref "Y2") (pin "3") (pinfunction "2_3") (pintype "passive"))
      (node (ref "Y2") (pin "4") (pinfunction "2_4") (pintype "passive"))
      (node (ref "Y2") (pin "5") (pinfunction "2_5") (pintype "passive"))
      (node (ref "Y3") (pin "2") (pinfunction "2_2") (pintype "passive"))
      (node (ref "Y3") (pin "3") (pinfunction "2_3") (pintype "passive"))
      (node (ref "Y3") (pin "4") (pinfunction "2_4") (pintype "passive"))
      (node (ref "Y3") (pin "5") (pinfunction "2_5") (pintype "passive"))
      (node (ref "Y4") (pin "2") (pinfunction "2_2") (pintype "passive"))
      (node (ref "Y4") (pin "3") (pinfunction "2_3") (pintype "passive"))
      (node (ref "Y4") (pin "4") (pinfunction "2_4") (pintype "passive"))
      (node (ref "Y4") (pin "5") (pinfunction "2_5") (pintype "passive"))
      (node (ref "Y5") (pin "2") (pinfunction "2_2") (pintype "passive"))
      (node (ref "Y5") (pin "3") (pinfunction "2_3") (pintype "passive"))
      (node (ref "Y5") (pin "4") (pinfunction "2_4") (pintype "passive"))
      (node (ref "Y5") (pin "5") (pinfunction "2_5") (pintype "passive"))
      (node (ref "Y6") (pin "2") (pinfunction "2_2") (pintype "passive"))
      (node (ref "Y6") (pin "3") (pinfunction "2_3") (pintype "passive"))
      (node (ref "Y6") (pin "4") (pinfunction "2_4") (pintype "passive"))
      (node (ref "Y6") (pin "5") (pinfunction "2_5") (pintype "passive"))
      (node (ref "Z1") (pin "2@1") (pinfunction "2_2@1") (pintype "passive"))
      (node (ref "Z1") (pin "2@2") (pinfunction "2_2@2") (pintype "passive"))
      (node (ref "Z1") (pin "2@3") (pinfunction "2_2@3") (pintype "passive"))
      (node (ref "Z1") (pin "2@4") (pinfunction "2_2@4") (pintype "passive"))
      (node (ref "Z2") (pin "2@1") (pinfunction "2_2@1") (pintype "passive"))
      (node (ref "Z2") (pin "2@2") (pinfunction "2_2@2") (pintype "passive"))
      (node (ref "Z2") (pin "2@3") (pinfunction "2_2@3") (pintype "passive"))
      (node (ref "Z2") (pin "2@4") (pinfunction "2_2@4") (pintype "passive"))
      (node (ref "Z3") (pin "2@1") (pinfunction "2_2@1") (pintype "passive"))
      (node (ref "Z3") (pin "2@2") (pinfunction "2_2@2") (pintype "passive"))
      (node (ref "Z3") (pin "2@3") (pinfunction "2_2@3") (pintype "passive"))
      (node (ref "Z3") (pin "2@4") (pinfunction "2_2@4") (pintype "passive"))
      (node (ref "Z4") (pin "2@1") (pinfunction "2_2@1") (pintype "passive"))
      (node (ref "Z4") (pin "2@2") (pinfunction "2_2@2") (pintype "passive"))
      (node (ref "Z4") (pin "2@3") (pinfunction "2_2@3") (pintype "passive"))
      (node (ref "Z4") (pin "2@4") (pinfunction "2_2@4") (pintype "passive"))
      (node (ref "Z5") (pin "2@1") (pinfunction "2_2@1") (pintype "passive"))
      (node (ref "Z5") (pin "2@2") (pinfunction "2_2@2") (pintype "passive"))
      (node (ref "Z5") (pin "2@3") (pinfunction "2_2@3") (pintype "passive"))
      (node (ref "Z5") (pin "2@4") (pinfunction "2_2@4") (pintype "passive"))
      (node (ref "Z6") (pin "2@1") (pinfunction "2_2@1") (pintype "passive"))
      (node (ref "Z6") (pin "2@2") (pinfunction "2_2@2") (pintype "passive"))
      (node (ref "Z6") (pin "2@3") (pinfunction "2_2@3") (pintype "passive"))
      (node (ref "Z6") (pin "2@4") (pinfunction "2_2@4") (pintype "passive"))
      (node (ref "ZED1") (pin "115") (pinfunction "GND_115") (pintype "power_in"))
      (node (ref "ZED1") (pin "116") (pinfunction "GND_116") (pintype "power_in"))
      (node (ref "ZED1") (pin "121") (pinfunction "GND_121") (pintype "power_in"))
      (node (ref "ZED1") (pin "122") (pinfunction "GND_122") (pintype "power_in"))
      (node (ref "ZED1") (pin "127") (pinfunction "GND_127") (pintype "power_in"))
      (node (ref "ZED1") (pin "128") (pinfunction "GND_128") (pintype "power_in"))
      (node (ref "ZED1") (pin "133") (pinfunction "GND_133") (pintype "power_in"))
      (node (ref "ZED1") (pin "134") (pinfunction "GND_134") (pintype "power_in"))
      (node (ref "ZED1") (pin "139") (pinfunction "GND_139") (pintype "power_in"))
      (node (ref "ZED1") (pin "140") (pinfunction "GND_140") (pintype "power_in"))
      (node (ref "ZED1") (pin "145") (pinfunction "GND_145") (pintype "power_in"))
      (node (ref "ZED1") (pin "146") (pinfunction "GND_146") (pintype "power_in"))
      (node (ref "ZED1") (pin "15") (pinfunction "GND_15") (pintype "power_in"))
      (node (ref "ZED1") (pin "151") (pinfunction "GND_151") (pintype "power_in"))
      (node (ref "ZED1") (pin "152") (pinfunction "GND_152") (pintype "power_in"))
      (node (ref "ZED1") (pin "16") (pinfunction "GND_16") (pintype "power_in"))
      (node (ref "ZED1") (pin "165") (pinfunction "GND_165") (pintype "power_in"))
      (node (ref "ZED1") (pin "166") (pinfunction "GND_166") (pintype "power_in"))
      (node (ref "ZED1") (pin "171") (pinfunction "GND_171") (pintype "power_in"))
      (node (ref "ZED1") (pin "172") (pinfunction "GND_172") (pintype "power_in"))
      (node (ref "ZED1") (pin "177") (pinfunction "GND_177") (pintype "power_in"))
      (node (ref "ZED1") (pin "185") (pinfunction "GND_185") (pintype "power_in"))
      (node (ref "ZED1") (pin "186") (pinfunction "GND_186") (pintype "power_in"))
      (node (ref "ZED1") (pin "191") (pinfunction "GND_191") (pintype "power_in"))
      (node (ref "ZED1") (pin "192") (pinfunction "GND_192") (pintype "power_in"))
      (node (ref "ZED1") (pin "21") (pinfunction "GND_21") (pintype "power_in"))
      (node (ref "ZED1") (pin "22") (pinfunction "GND_22") (pintype "power_in"))
      (node (ref "ZED1") (pin "27") (pinfunction "GND_27") (pintype "power_in"))
      (node (ref "ZED1") (pin "28") (pinfunction "GND_28") (pintype "power_in"))
      (node (ref "ZED1") (pin "33") (pinfunction "GND_33") (pintype "power_in"))
      (node (ref "ZED1") (pin "34") (pinfunction "GND_34") (pintype "power_in"))
      (node (ref "ZED1") (pin "39") (pinfunction "GND_39") (pintype "power_in"))
      (node (ref "ZED1") (pin "40") (pinfunction "GND_40") (pintype "power_in"))
      (node (ref "ZED1") (pin "45") (pinfunction "GND_45") (pintype "power_in"))
      (node (ref "ZED1") (pin "46") (pinfunction "GND_46") (pintype "power_in"))
      (node (ref "ZED1") (pin "51") (pinfunction "GND_51") (pintype "power_in"))
      (node (ref "ZED1") (pin "52") (pinfunction "GND_52") (pintype "power_in"))
      (node (ref "ZED1") (pin "65") (pinfunction "GND_65") (pintype "power_in"))
      (node (ref "ZED1") (pin "66") (pinfunction "GND_66") (pintype "power_in"))
      (node (ref "ZED1") (pin "71") (pinfunction "GND_71") (pintype "power_in"))
      (node (ref "ZED1") (pin "72") (pinfunction "GND_72") (pintype "power_in"))
      (node (ref "ZED1") (pin "77") (pinfunction "GND_77") (pintype "power_in"))
      (node (ref "ZED1") (pin "85") (pinfunction "GND_85") (pintype "power_in"))
      (node (ref "ZED1") (pin "86") (pinfunction "GND_86") (pintype "power_in"))
      (node (ref "ZED1") (pin "95") (pinfunction "GND_95") (pintype "power_in"))
      (node (ref "ZED1") (pin "96") (pinfunction "GND_96") (pintype "power_in"))
    )
    (net (code "7") (name "Net-(FB1-P$1)") (class "Default")
      (node (ref "C4") (pin "1") (pinfunction "1_1") (pintype "passive"))
      (node (ref "FB1") (pin "1") (pinfunction "P$1_1") (pintype "passive"))
      (node (ref "U3") (pin "5") (pinfunction "VCC_5") (pintype "power_in"))
      (node (ref "USB") (pin "VBUS") (pinfunction "VBUS_VBUS") (pintype "bidirectional"))
    )
    (net (code "8") (name "Net-(FB1-P$2)") (class "Default")
      (node (ref "FB1") (pin "2") (pinfunction "P$2_2") (pintype "passive"))
      (node (ref "U1") (pin "40") (pinfunction "VREGIN_40") (pintype "power_in"))
    )
    (net (code "9") (name "Net-(PAD1-P)") (class "Default")
      (node (ref "PAD1") (pin "1") (pinfunction "P_1") (pintype "passive"))
      (node (ref "ZED1") (pin "126") (pinfunction "_N_126") (pintype "bidirectional"))
    )
    (net (code "10") (name "Net-(PAD2-P)") (class "Default")
      (node (ref "PAD2") (pin "1") (pinfunction "P_1") (pintype "passive"))
      (node (ref "ZED1") (pin "124") (pinfunction "_P_124") (pintype "bidirectional"))
    )
    (net (code "11") (name "Net-(PAD3-P)") (class "Default")
      (node (ref "PAD3") (pin "1") (pinfunction "P_1") (pintype "passive"))
      (node (ref "ZED1") (pin "120") (pinfunction "_N_120") (pintype "bidirectional"))
    )
    (net (code "12") (name "Net-(PAD4-P)") (class "Default")
      (node (ref "PAD4") (pin "1") (pinfunction "P_1") (pintype "passive"))
      (node (ref "ZED1") (pin "118") (pinfunction "_P_118") (pintype "bidirectional"))
    )
    (net (code "13") (name "Net-(PAD7-P)") (class "Default")
      (node (ref "PAD7") (pin "1") (pinfunction "P_1") (pintype "passive"))
      (node (ref "ZED1") (pin "119") (pinfunction "_N_119") (pintype "bidirectional"))
    )
    (net (code "14") (name "Net-(PAD8-P)") (class "Default")
      (node (ref "PAD8") (pin "1") (pinfunction "P_1") (pintype "passive"))
      (node (ref "ZED1") (pin "117") (pinfunction "_P_117") (pintype "bidirectional"))
    )
    (net (code "15") (name "Net-(PAD9-P)") (class "Default")
      (node (ref "PAD9") (pin "1") (pinfunction "P_1") (pintype "passive"))
      (node (ref "ZED1") (pin "141") (pinfunction "_P_141") (pintype "bidirectional"))
    )
    (net (code "16") (name "Net-(PAD10-P)") (class "Default")
      (node (ref "PAD10") (pin "1") (pinfunction "P_1") (pintype "passive"))
      (node (ref "ZED1") (pin "143") (pinfunction "_N_143") (pintype "bidirectional"))
    )
    (net (code "17") (name "Net-(PAD13-P)") (class "Default")
      (node (ref "PAD13") (pin "1") (pinfunction "P_1") (pintype "passive"))
      (node (ref "ZED1") (pin "190") (pinfunction "_N_190") (pintype "bidirectional"))
    )
    (net (code "18") (name "Net-(PAD14-P)") (class "Default")
      (node (ref "PAD14") (pin "1") (pinfunction "P_1") (pintype "passive"))
      (node (ref "ZED1") (pin "188") (pinfunction "_P_188") (pintype "bidirectional"))
    )
    (net (code "19") (name "Net-(PAD15-P)") (class "Default")
      (node (ref "PAD15") (pin "1") (pinfunction "P_1") (pintype "passive"))
      (node (ref "ZED1") (pin "184") (pinfunction "_N_184") (pintype "bidirectional"))
    )
    (net (code "20") (name "Net-(PAD16-P)") (class "Default")
      (node (ref "PAD16") (pin "1") (pinfunction "P_1") (pintype "passive"))
      (node (ref "ZED1") (pin "182") (pinfunction "_P_182") (pintype "bidirectional"))
    )
    (net (code "21") (name "Net-(PAD19-P)") (class "Default")
      (node (ref "PAD19") (pin "1") (pinfunction "P_1") (pintype "passive"))
      (node (ref "ZED1") (pin "193") (pinfunction "_P_193") (pintype "bidirectional"))
    )
    (net (code "22") (name "Net-(PAD20-P)") (class "Default")
      (node (ref "PAD20") (pin "1") (pinfunction "P_1") (pintype "passive"))
      (node (ref "ZED1") (pin "195") (pinfunction "_N_195") (pintype "bidirectional"))
    )
    (net (code "23") (name "Net-(PAD21-P)") (class "Default")
      (node (ref "PAD21") (pin "1") (pinfunction "P_1") (pintype "passive"))
      (node (ref "ZED1") (pin "199") (pinfunction "_N_199") (pintype "bidirectional"))
    )
    (net (code "24") (name "Net-(PAD22-P)") (class "Default")
      (node (ref "PAD22") (pin "1") (pinfunction "P_1") (pintype "passive"))
      (node (ref "ZED1") (pin "197") (pinfunction "_P_197") (pintype "bidirectional"))
    )
    (net (code "25") (name "Net-(PAD25-P)") (class "Default")
      (node (ref "PAD25") (pin "1") (pinfunction "P_1") (pintype "passive"))
      (node (ref "ZED1") (pin "90") (pinfunction "_N_90") (pintype "bidirectional"))
    )
    (net (code "26") (name "Net-(PAD26-P)") (class "Default")
      (node (ref "PAD26") (pin "1") (pinfunction "P_1") (pintype "passive"))
      (node (ref "ZED1") (pin "88") (pinfunction "_P_88") (pintype "bidirectional"))
    )
    (net (code "27") (name "Net-(PAD27-P)") (class "Default")
      (node (ref "PAD27") (pin "1") (pinfunction "P_1") (pintype "passive"))
      (node (ref "ZED1") (pin "91") (pinfunction "_P_91") (pintype "bidirectional"))
    )
    (net (code "28") (name "Net-(PAD28-P)") (class "Default")
      (node (ref "PAD28") (pin "1") (pinfunction "P_1") (pintype "passive"))
      (node (ref "ZED1") (pin "93") (pinfunction "_N_93") (pintype "bidirectional"))
    )
    (net (code "29") (name "Net-(PAD31-P)") (class "Default")
      (node (ref "PAD31") (pin "1") (pinfunction "P_1") (pintype "passive"))
      (node (ref "ZED1") (pin "92") (pinfunction "_P_92") (pintype "bidirectional"))
    )
    (net (code "30") (name "Net-(PAD32-P)") (class "Default")
      (node (ref "PAD32") (pin "1") (pinfunction "P_1") (pintype "passive"))
      (node (ref "ZED1") (pin "94") (pinfunction "_N_94") (pintype "bidirectional"))
    )
    (net (code "31") (name "Net-(PAD33-P)") (class "Default")
      (node (ref "PAD33") (pin "1") (pinfunction "P_1") (pintype "passive"))
      (node (ref "ZED1") (pin "87") (pinfunction "_P_87") (pintype "bidirectional"))
    )
    (net (code "32") (name "Net-(PAD34-P)") (class "Default")
      (node (ref "PAD34") (pin "1") (pinfunction "P_1") (pintype "passive"))
      (node (ref "ZED1") (pin "89") (pinfunction "_N_89") (pintype "bidirectional"))
    )
    (net (code "33") (name "Net-(PAD37-P)") (class "Default")
      (node (ref "PAD37") (pin "1") (pinfunction "P_1") (pintype "passive"))
      (node (ref "ZED1") (pin "20") (pinfunction "_N_20") (pintype "bidirectional"))
    )
    (net (code "34") (name "Net-(PAD38-P)") (class "Default")
      (node (ref "PAD38") (pin "1") (pinfunction "P_1") (pintype "passive"))
      (node (ref "ZED1") (pin "18") (pinfunction "_P_18") (pintype "bidirectional"))
    )
    (net (code "35") (name "Net-(PAD39-P)") (class "Default")
      (node (ref "PAD39") (pin "1") (pinfunction "P_1") (pintype "passive"))
      (node (ref "ZED1") (pin "14") (pinfunction "_N_14") (pintype "bidirectional"))
    )
    (net (code "36") (name "Net-(PAD40-P)") (class "Default")
      (node (ref "PAD40") (pin "1") (pinfunction "P_1") (pintype "passive"))
      (node (ref "ZED1") (pin "12") (pinfunction "_P_12") (pintype "bidirectional"))
    )
    (net (code "37") (name "Net-(PAD43-P)") (class "Default")
      (node (ref "PAD43") (pin "1") (pinfunction "P_1") (pintype "passive"))
      (node (ref "ZED1") (pin "19") (pinfunction "_N_19") (pintype "bidirectional"))
    )
    (net (code "38") (name "Net-(PAD44-P)") (class "Default")
      (node (ref "PAD44") (pin "1") (pinfunction "P_1") (pintype "passive"))
      (node (ref "ZED1") (pin "17") (pinfunction "_P_17") (pintype "bidirectional"))
    )
    (net (code "39") (name "Net-(PAD45-P)") (class "Default")
      (node (ref "PAD45") (pin "1") (pinfunction "P_1") (pintype "passive"))
      (node (ref "ZED1") (pin "13") (pinfunction "_N_13") (pintype "bidirectional"))
    )
    (net (code "40") (name "Net-(PAD46-P)") (class "Default")
      (node (ref "PAD46") (pin "1") (pinfunction "P_1") (pintype "passive"))
      (node (ref "ZED1") (pin "11") (pinfunction "_P_11") (pintype "bidirectional"))
    )
    (net (code "41") (name "Net-(Q1-2)") (class "Default")
      (node (ref "C2") (pin "1") (pinfunction "1_1") (pintype "passive"))
      (node (ref "Q1") (pin "3") (pinfunction "2_3") (pintype "passive"))
      (node (ref "U1") (pin "2") (pinfunction "OSCO_2") (pintype "output"))
    )
    (net (code "42") (name "Net-(U1-DM)") (class "Default")
      (node (ref "U1") (pin "6") (pinfunction "DM_6") (pintype "bidirectional"))
      (node (ref "U3") (pin "2") (pinfunction "IO2_2") (pintype "bidirectional"))
      (node (ref "USB") (pin "D-") (pinfunction "D-_D-") (pintype "bidirectional"))
    )
    (net (code "43") (name "Net-(U1-DP)") (class "Default")
      (node (ref "U1") (pin "7") (pinfunction "DP_7") (pintype "bidirectional"))
      (node (ref "U3") (pin "1") (pinfunction "IO1_1") (pintype "bidirectional"))
      (node (ref "USB") (pin "D+") (pinfunction "D+_D+") (pintype "bidirectional"))
    )
    (net (code "44") (name "Net-(U1-EECLK)") (class "Default")
      (node (ref "R4") (pin "1") (pinfunction "1_1") (pintype "passive"))
      (node (ref "U1") (pin "44") (pinfunction "EECLK_44") (pintype "output"))
      (node (ref "U2") (pin "4") (pinfunction "CLK_4") (pintype "input"))
    )
    (net (code "45") (name "Net-(U1-EECS)") (class "Default")
      (node (ref "R3") (pin "1") (pinfunction "1_1") (pintype "passive"))
      (node (ref "U1") (pin "45") (pinfunction "EECS_45") (pintype "output"))
      (node (ref "U2") (pin "5") (pinfunction "CS_5") (pintype "input"))
    )
    (net (code "46") (name "Net-(U1-EEDATA)") (class "Default")
      (node (ref "R6") (pin "2") (pinfunction "2_2") (pintype "passive"))
      (node (ref "U1") (pin "43") (pinfunction "EEDATA_43") (pintype "bidirectional"))
      (node (ref "U2") (pin "3") (pinfunction "DI_3") (pintype "input"))
    )
    (net (code "47") (name "Net-(U1-OSCI)") (class "Default")
      (node (ref "C1") (pin "1") (pinfunction "1_1") (pintype "passive"))
      (node (ref "Q1") (pin "1") (pinfunction "1_1") (pintype "passive"))
      (node (ref "U1") (pin "1") (pinfunction "OSCI_1") (pintype "input"))
    )
    (net (code "48") (name "Net-(U1-REF)") (class "Default")
      (node (ref "R1") (pin "2") (pinfunction "2_2") (pintype "passive"))
      (node (ref "U1") (pin "5") (pinfunction "REF_5") (pintype "input"))
    )
    (net (code "49") (name "Net-(U1-RESET#)") (class "Default")
      (node (ref "C3") (pin "1") (pinfunction "1_1") (pintype "passive"))
      (node (ref "R2") (pin "1") (pinfunction "1_1") (pintype "passive"))
      (node (ref "U1") (pin "34") (pinfunction "RESET#_34") (pintype "input"))
    )
    (net (code "50") (name "Net-(U2-DO)") (class "Default")
      (node (ref "R5") (pin "1") (pinfunction "1_1") (pintype "passive"))
      (node (ref "R6") (pin "1") (pinfunction "1_1") (pintype "passive"))
      (node (ref "U2") (pin "1") (pinfunction "DO_1") (pintype "output"))
    )
    (net (code "51") (name "Net-(U3-IO3)") (class "Default")
      (node (ref "U3") (pin "4") (pinfunction "IO3_4") (pintype "bidirectional"))
      (node (ref "USB") (pin "ID") (pinfunction "USBID_ID") (pintype "bidirectional"))
    )
    (net (code "52") (name "Net-(X1-A)") (class "Default")
      (node (ref "X1") (pin "2") (pinfunction "A_2") (pintype "bidirectional"))
      (node (ref "ZED1") (pin "29") (pinfunction "_P_29") (pintype "bidirectional"))
    )
    (net (code "53") (name "Net-(X1-B)") (class "Default")
      (node (ref "X1") (pin "6") (pinfunction "B_6") (pintype "bidirectional"))
      (node (ref "ZED1") (pin "23") (pinfunction "_P_23") (pintype "bidirectional"))
    )
    (net (code "54") (name "Net-(X1-~{A})") (class "Default")
      (node (ref "X1") (pin "3") (pinfunction "~{A}_3") (pintype "bidirectional"))
      (node (ref "ZED1") (pin "31") (pinfunction "_N_31") (pintype "bidirectional"))
    )
    (net (code "55") (name "Net-(X1-~{B})") (class "Default")
      (node (ref "X1") (pin "5") (pinfunction "~{B}_5") (pintype "bidirectional"))
      (node (ref "ZED1") (pin "25") (pinfunction "_N_25") (pintype "bidirectional"))
    )
    (net (code "56") (name "Net-(X2-A)") (class "Default")
      (node (ref "X2") (pin "2") (pinfunction "A_2") (pintype "bidirectional"))
      (node (ref "ZED1") (pin "24") (pinfunction "_P_24") (pintype "bidirectional"))
    )
    (net (code "57") (name "Net-(X2-B)") (class "Default")
      (node (ref "X2") (pin "6") (pinfunction "B_6") (pintype "bidirectional"))
      (node (ref "ZED1") (pin "30") (pinfunction "_P_30") (pintype "bidirectional"))
    )
    (net (code "58") (name "Net-(X2-~{A})") (class "Default")
      (node (ref "X2") (pin "3") (pinfunction "~{A}_3") (pintype "bidirectional"))
      (node (ref "ZED1") (pin "26") (pinfunction "_N_26") (pintype "bidirectional"))
    )
    (net (code "59") (name "Net-(X2-~{B})") (class "Default")
      (node (ref "X2") (pin "5") (pinfunction "~{B}_5") (pintype "bidirectional"))
      (node (ref "ZED1") (pin "32") (pinfunction "_N_32") (pintype "bidirectional"))
    )
    (net (code "60") (name "Net-(X3-A)") (class "Default")
      (node (ref "X3") (pin "2") (pinfunction "A_2") (pintype "bidirectional"))
      (node (ref "ZED1") (pin "41") (pinfunction "_P_41") (pintype "bidirectional"))
    )
    (net (code "61") (name "Net-(X3-B)") (class "Default")
      (node (ref "X3") (pin "6") (pinfunction "B_6") (pintype "bidirectional"))
      (node (ref "ZED1") (pin "36") (pinfunction "_P_36") (pintype "bidirectional"))
    )
    (net (code "62") (name "Net-(X3-~{A})") (class "Default")
      (node (ref "X3") (pin "3") (pinfunction "~{A}_3") (pintype "bidirectional"))
      (node (ref "ZED1") (pin "43") (pinfunction "_N_43") (pintype "bidirectional"))
    )
    (net (code "63") (name "Net-(X3-~{B})") (class "Default")
      (node (ref "X3") (pin "5") (pinfunction "~{B}_5") (pintype "bidirectional"))
      (node (ref "ZED1") (pin "38") (pinfunction "_N_38") (pintype "bidirectional"))
    )
    (net (code "64") (name "Net-(X4-A)") (class "Default")
      (node (ref "X4") (pin "2") (pinfunction "A_2") (pintype "bidirectional"))
      (node (ref "ZED1") (pin "130") (pinfunction "_P_130") (pintype "bidirectional"))
    )
    (net (code "65") (name "Net-(X4-B)") (class "Default")
      (node (ref "X4") (pin "6") (pinfunction "B_6") (pintype "bidirectional"))
      (node (ref "ZED1") (pin "136") (pinfunction "_P_136") (pintype "bidirectional"))
    )
    (net (code "66") (name "Net-(X4-~{A})") (class "Default")
      (node (ref "X4") (pin "3") (pinfunction "~{A}_3") (pintype "bidirectional"))
      (node (ref "ZED1") (pin "132") (pinfunction "_N_132") (pintype "bidirectional"))
    )
    (net (code "67") (name "Net-(X4-~{B})") (class "Default")
      (node (ref "X4") (pin "5") (pinfunction "~{B}_5") (pintype "bidirectional"))
      (node (ref "ZED1") (pin "138") (pinfunction "_N_138") (pintype "bidirectional"))
    )
    (net (code "68") (name "Net-(X5-A)") (class "Default")
      (node (ref "X5") (pin "2") (pinfunction "A_2") (pintype "bidirectional"))
      (node (ref "ZED1") (pin "49") (pinfunction "_N_49") (pintype "bidirectional"))
    )
    (net (code "69") (name "Net-(X5-B)") (class "Default")
      (node (ref "X5") (pin "6") (pinfunction "B_6") (pintype "bidirectional"))
      (node (ref "ZED1") (pin "53") (pinfunction "_P_53") (pintype "bidirectional"))
    )
    (net (code "70") (name "Net-(X5-~{A})") (class "Default")
      (node (ref "X5") (pin "3") (pinfunction "~{A}_3") (pintype "bidirectional"))
      (node (ref "ZED1") (pin "47") (pinfunction "_P_47") (pintype "bidirectional"))
    )
    (net (code "71") (name "Net-(X5-~{B})") (class "Default")
      (node (ref "X5") (pin "5") (pinfunction "~{B}_5") (pintype "bidirectional"))
      (node (ref "ZED1") (pin "55") (pinfunction "_N_55") (pintype "bidirectional"))
    )
    (net (code "72") (name "Net-(X6-A)") (class "Default")
      (node (ref "X6") (pin "2") (pinfunction "A_2") (pintype "bidirectional"))
      (node (ref "ZED1") (pin "42") (pinfunction "_P_42") (pintype "bidirectional"))
    )
    (net (code "73") (name "Net-(X6-B)") (class "Default")
      (node (ref "X6") (pin "6") (pinfunction "B_6") (pintype "bidirectional"))
      (node (ref "ZED1") (pin "48") (pinfunction "_P_48") (pintype "bidirectional"))
    )
    (net (code "74") (name "Net-(X6-~{A})") (class "Default")
      (node (ref "X6") (pin "3") (pinfunction "~{A}_3") (pintype "bidirectional"))
      (node (ref "ZED1") (pin "44") (pinfunction "_N_44") (pintype "bidirectional"))
    )
    (net (code "75") (name "Net-(X6-~{B})") (class "Default")
      (node (ref "X6") (pin "5") (pinfunction "~{B}_5") (pintype "bidirectional"))
      (node (ref "ZED1") (pin "50") (pinfunction "_N_50") (pintype "bidirectional"))
    )
    (net (code "76") (name "Net-(X7-A)") (class "Default")
      (node (ref "X7") (pin "2") (pinfunction "A_2") (pintype "bidirectional"))
      (node (ref "ZED1") (pin "61") (pinfunction "_P_61") (pintype "bidirectional"))
    )
    (net (code "77") (name "Net-(X7-B)") (class "Default")
      (node (ref "X7") (pin "6") (pinfunction "B_6") (pintype "bidirectional"))
      (node (ref "ZED1") (pin "54") (pinfunction "_P_54") (pintype "bidirectional"))
    )
    (net (code "78") (name "Net-(X7-~{A})") (class "Default")
      (node (ref "X7") (pin "3") (pinfunction "~{A}_3") (pintype "bidirectional"))
      (node (ref "ZED1") (pin "63") (pinfunction "_N_63") (pintype "bidirectional"))
    )
    (net (code "79") (name "Net-(X7-~{B})") (class "Default")
      (node (ref "X7") (pin "5") (pinfunction "~{B}_5") (pintype "bidirectional"))
      (node (ref "ZED1") (pin "56") (pinfunction "_N_56") (pintype "bidirectional"))
    )
    (net (code "80") (name "Net-(X8-A)") (class "Default")
      (node (ref "X8") (pin "2") (pinfunction "A_2") (pintype "bidirectional"))
      (node (ref "ZED1") (pin "154") (pinfunction "_P_154") (pintype "bidirectional"))
    )
    (net (code "81") (name "Net-(X8-B)") (class "Default")
      (node (ref "X8") (pin "6") (pinfunction "B_6") (pintype "bidirectional"))
      (node (ref "ZED1") (pin "148") (pinfunction "_P_148") (pintype "bidirectional"))
    )
    (net (code "82") (name "Net-(X8-~{A})") (class "Default")
      (node (ref "X8") (pin "3") (pinfunction "~{A}_3") (pintype "bidirectional"))
      (node (ref "ZED1") (pin "156") (pinfunction "_N_156") (pintype "bidirectional"))
    )
    (net (code "83") (name "Net-(X8-~{B})") (class "Default")
      (node (ref "X8") (pin "5") (pinfunction "~{B}_5") (pintype "bidirectional"))
      (node (ref "ZED1") (pin "150") (pinfunction "_N_150") (pintype "bidirectional"))
    )
    (net (code "84") (name "Net-(X9-A)") (class "Default")
      (node (ref "X9") (pin "2") (pinfunction "A_2") (pintype "bidirectional"))
      (node (ref "ZED1") (pin "181") (pinfunction "_P_181") (pintype "bidirectional"))
    )
    (net (code "85") (name "Net-(X9-B)") (class "Default")
      (node (ref "X9") (pin "6") (pinfunction "B_6") (pintype "bidirectional"))
      (node (ref "ZED1") (pin "174") (pinfunction "_P_174") (pintype "bidirectional"))
    )
    (net (code "86") (name "Net-(X9-~{A})") (class "Default")
      (node (ref "X9") (pin "3") (pinfunction "~{A}_3") (pintype "bidirectional"))
      (node (ref "ZED1") (pin "183") (pinfunction "_N_183") (pintype "bidirectional"))
    )
    (net (code "87") (name "Net-(X9-~{B})") (class "Default")
      (node (ref "X9") (pin "5") (pinfunction "~{B}_5") (pintype "bidirectional"))
      (node (ref "ZED1") (pin "176") (pinfunction "_N_176") (pintype "bidirectional"))
    )
    (net (code "88") (name "Net-(X10-A)") (class "Default")
      (node (ref "X10") (pin "2") (pinfunction "A_2") (pintype "bidirectional"))
      (node (ref "ZED1") (pin "74") (pinfunction "_P_74") (pintype "bidirectional"))
    )
    (net (code "89") (name "Net-(X10-B)") (class "Default")
      (node (ref "X10") (pin "6") (pinfunction "B_6") (pintype "bidirectional"))
      (node (ref "ZED1") (pin "82") (pinfunction "_P_82") (pintype "bidirectional"))
    )
    (net (code "90") (name "Net-(X10-~{A})") (class "Default")
      (node (ref "X10") (pin "3") (pinfunction "~{A}_3") (pintype "bidirectional"))
      (node (ref "ZED1") (pin "76") (pinfunction "_N_76") (pintype "bidirectional"))
    )
    (net (code "91") (name "Net-(X10-~{B})") (class "Default")
      (node (ref "X10") (pin "5") (pinfunction "~{B}_5") (pintype "bidirectional"))
      (node (ref "ZED1") (pin "84") (pinfunction "_N_84") (pintype "bidirectional"))
    )
    (net (code "92") (name "Net-(X11-A)") (class "Default")
      (node (ref "X11") (pin "2") (pinfunction "A_2") (pintype "bidirectional"))
      (node (ref "ZED1") (pin "67") (pinfunction "_P_67") (pintype "bidirectional"))
    )
    (net (code "93") (name "Net-(X11-B)") (class "Default")
      (node (ref "X11") (pin "6") (pinfunction "B_6") (pintype "bidirectional"))
      (node (ref "ZED1") (pin "73") (pinfunction "_P_73") (pintype "bidirectional"))
    )
    (net (code "94") (name "Net-(X11-~{A})") (class "Default")
      (node (ref "X11") (pin "3") (pinfunction "~{A}_3") (pintype "bidirectional"))
      (node (ref "ZED1") (pin "69") (pinfunction "_N_69") (pintype "bidirectional"))
    )
    (net (code "95") (name "Net-(X11-~{B})") (class "Default")
      (node (ref "X11") (pin "5") (pinfunction "~{B}_5") (pintype "bidirectional"))
      (node (ref "ZED1") (pin "75") (pinfunction "_N_75") (pintype "bidirectional"))
    )
    (net (code "96") (name "Net-(X12-A)") (class "Default")
      (node (ref "X12") (pin "2") (pinfunction "A_2") (pintype "bidirectional"))
      (node (ref "ZED1") (pin "62") (pinfunction "_P_62") (pintype "bidirectional"))
    )
    (net (code "97") (name "Net-(X12-B)") (class "Default")
      (node (ref "X12") (pin "6") (pinfunction "B_6") (pintype "bidirectional"))
      (node (ref "ZED1") (pin "68") (pinfunction "_P_68") (pintype "bidirectional"))
    )
    (net (code "98") (name "Net-(X12-~{A})") (class "Default")
      (node (ref "X12") (pin "3") (pinfunction "~{A}_3") (pintype "bidirectional"))
      (node (ref "ZED1") (pin "64") (pinfunction "_N_64") (pintype "bidirectional"))
    )
    (net (code "99") (name "Net-(X12-~{B})") (class "Default")
      (node (ref "X12") (pin "5") (pinfunction "~{B}_5") (pintype "bidirectional"))
      (node (ref "ZED1") (pin "70") (pinfunction "_N_70") (pintype "bidirectional"))
    )
    (net (code "100") (name "Net-(ZED1AK-_N)") (class "Default")
      (node (ref "Y6") (pin "1") (pinfunction "1_1") (pintype "passive"))
      (node (ref "ZED1") (pin "125") (pinfunction "_N_125") (pintype "bidirectional"))
    )
    (net (code "101") (name "Net-(ZED1AK-_P)") (class "Default")
      (node (ref "Y5") (pin "1") (pinfunction "1_1") (pintype "passive"))
      (node (ref "ZED1") (pin "123") (pinfunction "_P_123") (pintype "bidirectional"))
    )
    (net (code "102") (name "Net-(ZED1AR-_N)") (class "Default")
      (node (ref "Z6") (pin "1") (pinfunction "1_1") (pintype "passive"))
      (node (ref "ZED1") (pin "144") (pinfunction "_N_144") (pintype "bidirectional"))
    )
    (net (code "103") (name "Net-(ZED1AR-_P)") (class "Default")
      (node (ref "Z5") (pin "1") (pinfunction "1_1") (pintype "passive"))
      (node (ref "ZED1") (pin "142") (pinfunction "_P_142") (pintype "bidirectional"))
    )
    (net (code "104") (name "Net-(ZED1AX-_N)") (class "Default")
      (node (ref "Z4") (pin "1") (pinfunction "1_1") (pintype "passive"))
      (node (ref "ZED1") (pin "164") (pinfunction "_N_164") (pintype "bidirectional"))
    )
    (net (code "105") (name "Net-(ZED1AX-_P)") (class "Default")
      (node (ref "Z3") (pin "1") (pinfunction "1_1") (pintype "passive"))
      (node (ref "ZED1") (pin "162") (pinfunction "_P_162") (pintype "bidirectional"))
    )
    (net (code "106") (name "Net-(ZED1AY-_N)") (class "Default")
      (node (ref "Y4") (pin "1") (pinfunction "1_1") (pintype "passive"))
      (node (ref "ZED1") (pin "169") (pinfunction "_N_169") (pintype "bidirectional"))
    )
    (net (code "107") (name "Net-(ZED1AY-_P)") (class "Default")
      (node (ref "Y3") (pin "1") (pinfunction "1_1") (pintype "passive"))
      (node (ref "ZED1") (pin "167") (pinfunction "_P_167") (pintype "bidirectional"))
    )
    (net (code "108") (name "Net-(ZED1AZ-_N)") (class "Default")
      (node (ref "Z1") (pin "1") (pinfunction "1_1") (pintype "passive"))
      (node (ref "ZED1") (pin "170") (pinfunction "_N_170") (pintype "bidirectional"))
    )
    (net (code "109") (name "Net-(ZED1AZ-_P)") (class "Default")
      (node (ref "Z2") (pin "1") (pinfunction "1_1") (pintype "passive"))
      (node (ref "ZED1") (pin "168") (pinfunction "_P_168") (pintype "bidirectional"))
    )
    (net (code "110") (name "Net-(ZED1BA-_N)") (class "Default")
      (node (ref "Y1") (pin "1") (pinfunction "1_1") (pintype "passive"))
      (node (ref "ZED1") (pin "175") (pinfunction "_N_175") (pintype "bidirectional"))
    )
    (net (code "111") (name "Net-(ZED1BA-_P)") (class "Default")
      (node (ref "Y2") (pin "1") (pinfunction "1_1") (pintype "passive"))
      (node (ref "ZED1") (pin "173") (pinfunction "_P_173") (pintype "bidirectional"))
    )
    (net (code "112") (name "PMOD_A_VCC") (class "Default")
      (node (ref "JP1") (pin "1") (pinfunction "1_1") (pintype "passive"))
      (node (ref "PAD12") (pin "1") (pinfunction "P_1") (pintype "passive"))
      (node (ref "PAD6") (pin "1") (pinfunction "P_1") (pintype "passive"))
    )
    (net (code "113") (name "PMOD_B_VCC") (class "Default")
      (node (ref "JP2") (pin "1") (pinfunction "1_1") (pintype "passive"))
      (node (ref "PAD18") (pin "1") (pinfunction "P_1") (pintype "passive"))
      (node (ref "PAD24") (pin "1") (pinfunction "P_1") (pintype "passive"))
    )
    (net (code "114") (name "PMOD_C_VCC") (class "Default")
      (node (ref "JP3") (pin "2") (pinfunction "2_2") (pintype "passive"))
      (node (ref "PAD30") (pin "1") (pinfunction "P_1") (pintype "passive"))
      (node (ref "PAD36") (pin "1") (pinfunction "P_1") (pintype "passive"))
    )
    (net (code "115") (name "PMOD_D_VCC") (class "Default")
      (node (ref "JP4") (pin "2") (pinfunction "2_2") (pintype "passive"))
      (node (ref "PAD42") (pin "1") (pinfunction "P_1") (pintype "passive"))
      (node (ref "PAD48") (pin "1") (pinfunction "P_1") (pintype "passive"))
    )
    (net (code "116") (name "VCCA") (class "Default")
      (node (ref "C6") (pin "1") (pinfunction "1_1") (pintype "passive"))
      (node (ref "U1") (pin "37") (pinfunction "VCCA_37") (pintype "output"))
    )
    (net (code "117") (name "VCCD") (class "Default")
      (node (ref "FB2") (pin "1") (pinfunction "P$1_1") (pintype "passive"))
      (node (ref "FB3") (pin "1") (pinfunction "P$1_1") (pintype "passive"))
      (node (ref "R2") (pin "2") (pinfunction "2_2") (pintype "passive"))
      (node (ref "R3") (pin "2") (pinfunction "2_2") (pintype "passive"))
      (node (ref "R4") (pin "2") (pinfunction "2_2") (pintype "passive"))
      (node (ref "R5") (pin "2") (pinfunction "2_2") (pintype "passive"))
      (node (ref "U1") (pin "12") (pinfunction "VCCIO_12") (pintype "power_in"))
      (node (ref "U1") (pin "24") (pinfunction "VCCIO_24") (pintype "power_in"))
      (node (ref "U1") (pin "39") (pinfunction "VCCD_39") (pintype "power_in"))
      (node (ref "U1") (pin "46") (pinfunction "VCCIO_46") (pintype "power_in"))
      (node (ref "U2") (pin "6") (pinfunction "VCC_6") (pintype "power_in"))
    )
    (net (code "118") (name "VCCO_13") (class "Default")
      (node (ref "JP2") (pin "2") (pinfunction "2_2") (pintype "passive"))
      (node (ref "ZED1") (pin "198") (pinfunction "VCCO_13_198") (pintype "power_in"))
    )
    (net (code "119") (name "VCCO_34") (class "Default")
      (node (ref "JP3") (pin "1") (pinfunction "1_1") (pintype "passive"))
      (node (ref "ZED1") (pin "78") (pinfunction "VCCO_34_78") (pintype "power_in"))
      (node (ref "ZED1") (pin "79") (pinfunction "VCCO_34_79") (pintype "power_in"))
      (node (ref "ZED1") (pin "80") (pinfunction "VCCO_34_80") (pintype "power_in"))
    )
    (net (code "120") (name "VCCO_35") (class "Default")
      (node (ref "JP2") (pin "3") (pinfunction "3_3") (pintype "passive"))
      (node (ref "ZED1") (pin "178") (pinfunction "VCCO_35_178") (pintype "power_in"))
      (node (ref "ZED1") (pin "179") (pinfunction "VCCO_35_179") (pintype "power_in"))
      (node (ref "ZED1") (pin "180") (pinfunction "VCCO_35_180") (pintype "power_in"))
    )
    (net (code "121") (name "VCORE") (class "Default")
      (node (ref "C5") (pin "1") (pinfunction "1_1") (pintype "passive"))
      (node (ref "U1") (pin "38") (pinfunction "VCORE_38") (pintype "output"))
    )
    (net (code "122") (name "VIN_HDR") (class "Default")
      (node (ref "JP1") (pin "2") (pinfunction "2_2") (pintype "passive"))
      (node (ref "JP4") (pin "1") (pinfunction "1_1") (pintype "passive"))
      (node (ref "ZED1") (pin "112") (pinfunction "VIN_HDR_112") (pintype "power_in"))
      (node (ref "ZED1") (pin "157") (pinfunction "VIN_HDR_157") (pintype "power_in"))
      (node (ref "ZED1") (pin "158") (pinfunction "VIN_HDR_158") (pintype "power_in"))
      (node (ref "ZED1") (pin "159") (pinfunction "VIN_HDR_159") (pintype "power_in"))
      (node (ref "ZED1") (pin "160") (pinfunction "VIN_HDR_160") (pintype "power_in"))
      (node (ref "ZED1") (pin "57") (pinfunction "VIN_HDR_57") (pintype "power_in"))
      (node (ref "ZED1") (pin "58") (pinfunction "VIN_HDR_58") (pintype "power_in"))
      (node (ref "ZED1") (pin "59") (pinfunction "VIN_HDR_59") (pintype "power_in"))
      (node (ref "ZED1") (pin "60") (pinfunction "VIN_HDR_60") (pintype "power_in"))
    )
    (net (code "123") (name "VPHY") (class "Default")
      (node (ref "C7") (pin "1") (pinfunction "1_1") (pintype "passive"))
      (node (ref "C8") (pin "1") (pinfunction "1_1") (pintype "passive"))
      (node (ref "FB2") (pin "2") (pinfunction "P$2_2") (pintype "passive"))
      (node (ref "U1") (pin "3") (pinfunction "VPHY_3") (pintype "power_in"))
    )
    (net (code "124") (name "VPLL") (class "Default")
      (node (ref "C10") (pin "1") (pinfunction "1_1") (pintype "passive"))
      (node (ref "C9") (pin "1") (pinfunction "1_1") (pintype "passive"))
      (node (ref "FB3") (pin "2") (pinfunction "P$2_2") (pintype "passive"))
      (node (ref "U1") (pin "8") (pinfunction "VPLL_8") (pintype "power_in"))
    )
    (net (code "125") (name "unconnected-(U1-ACBUS0-Pad21)") (class "Default")
      (node (ref "U1") (pin "21") (pinfunction "ACBUS0_21") (pintype "bidirectional"))
    )
    (net (code "126") (name "unconnected-(U1-ACBUS1-Pad25)") (class "Default")
      (node (ref "U1") (pin "25") (pinfunction "ACBUS1_25") (pintype "bidirectional"))
    )
    (net (code "127") (name "unconnected-(U1-ACBUS2-Pad26)") (class "Default")
      (node (ref "U1") (pin "26") (pinfunction "ACBUS2_26") (pintype "bidirectional"))
    )
    (net (code "128") (name "unconnected-(U1-ACBUS3-Pad27)") (class "Default")
      (node (ref "U1") (pin "27") (pinfunction "ACBUS3_27") (pintype "bidirectional"))
    )
    (net (code "129") (name "unconnected-(U1-ACBUS4-Pad28)") (class "Default")
      (node (ref "U1") (pin "28") (pinfunction "ACBUS4_28") (pintype "bidirectional"))
    )
    (net (code "130") (name "unconnected-(U1-ACBUS5-Pad29)") (class "Default")
      (node (ref "U1") (pin "29") (pinfunction "ACBUS5_29") (pintype "bidirectional"))
    )
    (net (code "131") (name "unconnected-(U1-ACBUS6-Pad30)") (class "Default")
      (node (ref "U1") (pin "30") (pinfunction "ACBUS6_30") (pintype "bidirectional"))
    )
    (net (code "132") (name "unconnected-(U1-ACBUS7-Pad31)") (class "Default")
      (node (ref "U1") (pin "31") (pinfunction "ACBUS7_31") (pintype "bidirectional"))
    )
    (net (code "133") (name "unconnected-(U1-ACBUS8-Pad32)") (class "Default")
      (node (ref "U1") (pin "32") (pinfunction "ACBUS8_32") (pintype "bidirectional"))
    )
    (net (code "134") (name "unconnected-(U1-ACBUS9-Pad33)") (class "Default")
      (node (ref "U1") (pin "33") (pinfunction "ACBUS9_33") (pintype "bidirectional"))
    )
    (net (code "135") (name "unconnected-(U1-ADBUS4-Pad17)") (class "Default")
      (node (ref "U1") (pin "17") (pinfunction "ADBUS4_17") (pintype "output"))
    )
    (net (code "136") (name "unconnected-(U1-ADBUS5-Pad18)") (class "Default")
      (node (ref "U1") (pin "18") (pinfunction "ADBUS5_18") (pintype "input"))
    )
    (net (code "137") (name "unconnected-(U1-ADBUS6-Pad19)") (class "Default")
      (node (ref "U1") (pin "19") (pinfunction "ADBUS6_19") (pintype "input"))
    )
    (net (code "138") (name "unconnected-(U1-ADBUS7-Pad20)") (class "Default")
      (node (ref "U1") (pin "20") (pinfunction "ADBUS7_20") (pintype "input"))
    )
    (net (code "139") (name "unconnected-(U1-TEST-Pad42)") (class "Default")
      (node (ref "U1") (pin "42") (pinfunction "TEST_42") (pintype "input"))
    )
    (net (code "140") (name "unconnected-(ZED1AF-_N-Pad83)") (class "Default")
      (node (ref "ZED1") (pin "83") (pinfunction "_N_83") (pintype "bidirectional"))
    )
    (net (code "141") (name "unconnected-(ZED1AF-_P-Pad81)") (class "Default")
      (node (ref "ZED1") (pin "81") (pinfunction "_P_81") (pintype "bidirectional"))
    )
    (net (code "142") (name "unconnected-(ZED1AH-_0-Pad9)") (class "Default")
      (node (ref "ZED1") (pin "9") (pinfunction "_0_9") (pintype "bidirectional"))
    )
    (net (code "143") (name "unconnected-(ZED1AH-_1-Pad10)") (class "Default")
      (node (ref "ZED1") (pin "10") (pinfunction "_1_10") (pintype "bidirectional"))
    )
    (net (code "144") (name "unconnected-(ZED1AM-_N-Pad131)") (class "Default")
      (node (ref "ZED1") (pin "131") (pinfunction "_N_131") (pintype "bidirectional"))
    )
    (net (code "145") (name "unconnected-(ZED1AM-_P-Pad129)") (class "Default")
      (node (ref "ZED1") (pin "129") (pinfunction "_P_129") (pintype "bidirectional"))
    )
    (net (code "146") (name "unconnected-(ZED1AO-_N-Pad137)") (class "Default")
      (node (ref "ZED1") (pin "137") (pinfunction "_N_137") (pintype "bidirectional"))
    )
    (net (code "147") (name "unconnected-(ZED1AO-_P-Pad135)") (class "Default")
      (node (ref "ZED1") (pin "135") (pinfunction "_P_135") (pintype "bidirectional"))
    )
    (net (code "148") (name "unconnected-(ZED1AS-_N-Pad149)") (class "Default")
      (node (ref "ZED1") (pin "149") (pinfunction "_N_149") (pintype "bidirectional"))
    )
    (net (code "149") (name "unconnected-(ZED1AS-_P-Pad147)") (class "Default")
      (node (ref "ZED1") (pin "147") (pinfunction "_P_147") (pintype "bidirectional"))
    )
    (net (code "150") (name "unconnected-(ZED1AU-_N-Pad155)") (class "Default")
      (node (ref "ZED1") (pin "155") (pinfunction "_N_155") (pintype "bidirectional"))
    )
    (net (code "151") (name "unconnected-(ZED1AU-_P-Pad153)") (class "Default")
      (node (ref "ZED1") (pin "153") (pinfunction "_P_153") (pintype "bidirectional"))
    )
    (net (code "152") (name "unconnected-(ZED1AW-_N-Pad163)") (class "Default")
      (node (ref "ZED1") (pin "163") (pinfunction "_N_163") (pintype "bidirectional"))
    )
    (net (code "153") (name "unconnected-(ZED1AW-_P-Pad161)") (class "Default")
      (node (ref "ZED1") (pin "161") (pinfunction "_P_161") (pintype "bidirectional"))
    )
    (net (code "154") (name "unconnected-(ZED1BE-_N-Pad189)") (class "Default")
      (node (ref "ZED1") (pin "189") (pinfunction "_N_189") (pintype "bidirectional"))
    )
    (net (code "155") (name "unconnected-(ZED1BE-_P-Pad187)") (class "Default")
      (node (ref "ZED1") (pin "187") (pinfunction "_P_187") (pintype "bidirectional"))
    )
    (net (code "156") (name "unconnected-(ZED1BG-_0-Pad113)") (class "Default")
      (node (ref "ZED1") (pin "113") (pinfunction "_0_113") (pintype "bidirectional"))
    )
    (net (code "157") (name "unconnected-(ZED1BG-_1-Pad114)") (class "Default")
      (node (ref "ZED1") (pin "114") (pinfunction "_1_114") (pintype "bidirectional"))
    )
    (net (code "158") (name "unconnected-(ZED1BH-_N-Pad99)") (class "Default")
      (node (ref "ZED1") (pin "99") (pinfunction "_N_99") (pintype "bidirectional"))
    )
    (net (code "159") (name "unconnected-(ZED1BH-_P-Pad97)") (class "Default")
      (node (ref "ZED1") (pin "97") (pinfunction "_P_97") (pintype "bidirectional"))
    )
    (net (code "160") (name "unconnected-(ZED1BI-FPGA_DONE-Pad8)") (class "Default")
      (node (ref "ZED1") (pin "8") (pinfunction "FPGA_DONE_8") (pintype "output"))
    )
    (net (code "161") (name "unconnected-(ZED1BI-PG_MODULE-Pad111)") (class "Default")
      (node (ref "ZED1") (pin "111") (pinfunction "PG_MODULE_111") (pintype "output"))
    )
    (net (code "162") (name "unconnected-(ZED1BI-PWR_ENABLE-Pad5)") (class "Default")
      (node (ref "ZED1") (pin "5") (pinfunction "PWR_ENABLE_5") (pintype "input"))
    )
    (net (code "163") (name "unconnected-(ZED1BI-~{CARRIER_SRST}-Pad6)") (class "Default")
      (node (ref "ZED1") (pin "6") (pinfunction "~{CARRIER_SRST}_6") (pintype "output"))
    )
    (net (code "164") (name "unconnected-(ZED1BI-~{INIT}-Pad109)") (class "Default")
      (node (ref "ZED1") (pin "109") (pinfunction "~{INIT}_109") (pintype "input"))
    )
    (net (code "165") (name "unconnected-(ZED1BI-~{PROGRAM}-Pad110)") (class "Default")
      (node (ref "ZED1") (pin "110") (pinfunction "~{PROGRAM}_110") (pintype "input"))
    )
    (net (code "166") (name "unconnected-(ZED1F-_N-Pad196)") (class "Default")
      (node (ref "ZED1") (pin "196") (pinfunction "_N_196") (pintype "bidirectional"))
    )
    (net (code "167") (name "unconnected-(ZED1F-_P-Pad194)") (class "Default")
      (node (ref "ZED1") (pin "194") (pinfunction "_P_194") (pintype "bidirectional"))
    )
    (net (code "168") (name "unconnected-(ZED1H-_0-Pad200)") (class "Default")
      (node (ref "ZED1") (pin "200") (pinfunction "_0_200") (pintype "bidirectional"))
    )
    (net (code "169") (name "unconnected-(ZED1I-_N-Pad100)") (class "Default")
      (node (ref "ZED1") (pin "100") (pinfunction "_N_100") (pintype "bidirectional"))
    )
    (net (code "170") (name "unconnected-(ZED1I-_P-Pad98)") (class "Default")
      (node (ref "ZED1") (pin "98") (pinfunction "_P_98") (pintype "bidirectional"))
    )
    (net (code "171") (name "unconnected-(ZED1R-_N-Pad37)") (class "Default")
      (node (ref "ZED1") (pin "37") (pinfunction "_N_37") (pintype "bidirectional"))
    )
    (net (code "172") (name "unconnected-(ZED1R-_P-Pad35)") (class "Default")
      (node (ref "ZED1") (pin "35") (pinfunction "_P_35") (pintype "bidirectional"))
    )
  )
)
